# core_logique.net
KiCad netlist of a schematic drawn in Altium Designer
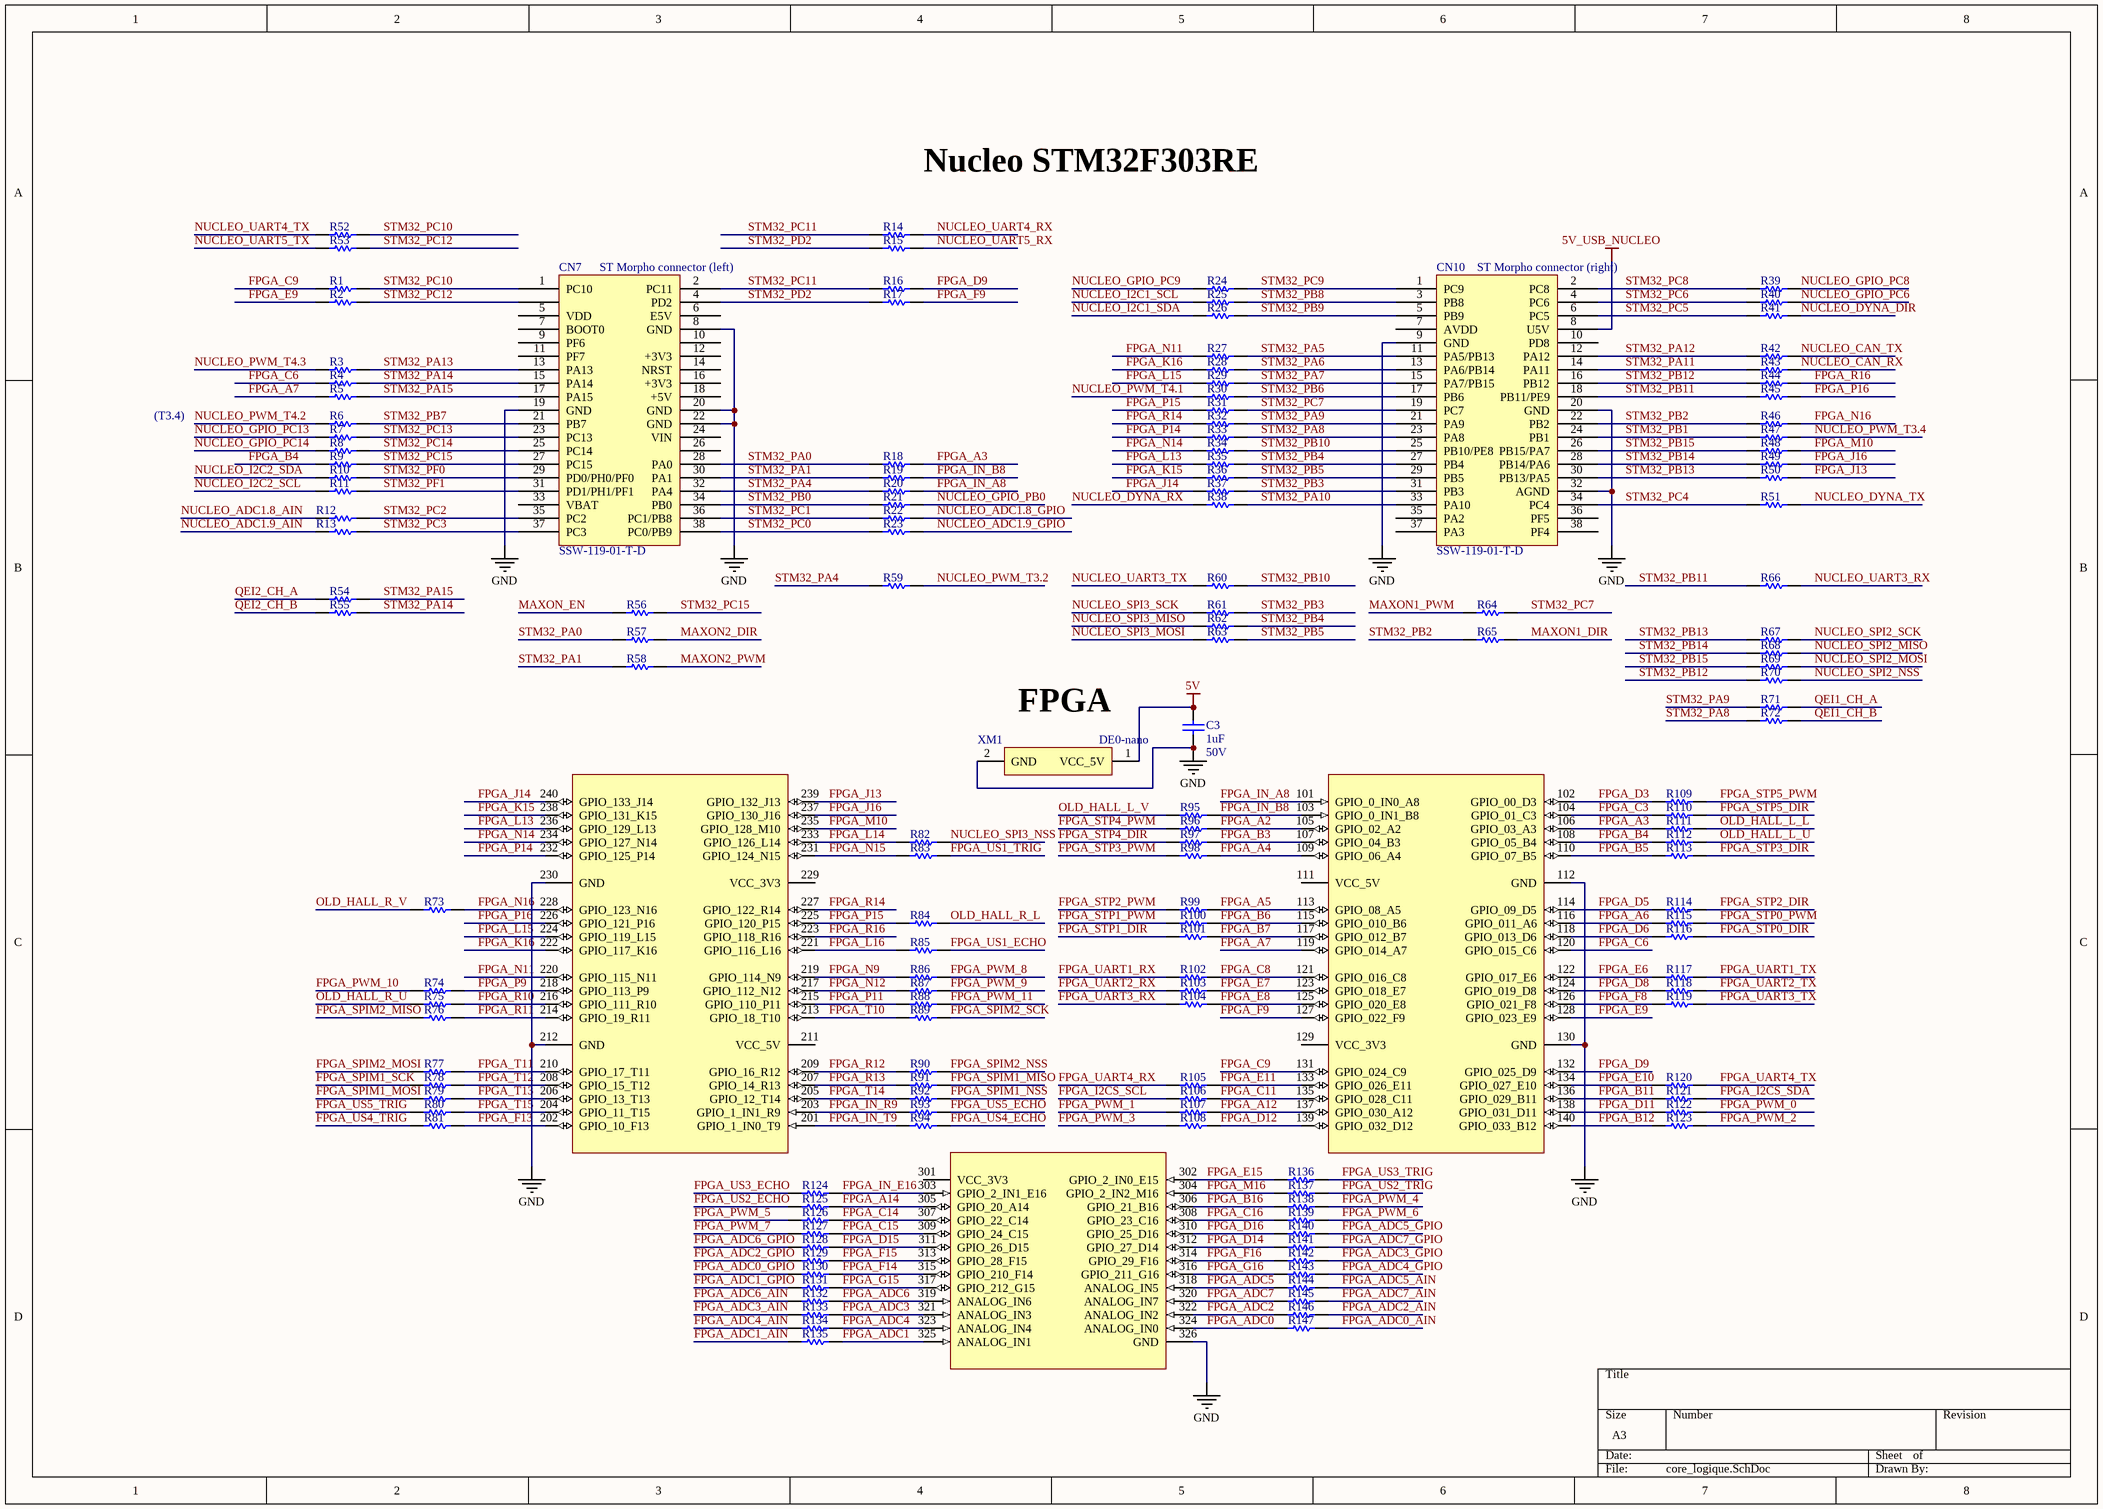
[diagram p0: core_logique.SchDoc]

(export (version "E")
  (design (tool "Eeschema 10.0.6"))
  (components
    (comp (ref "C3")
      (value "1uF")
      (footprint "WCAP-CSGP_0805, 2x1.25x1.25")
      (description "CAP CER 1uF 50V X7R 0805")
      (fields
        (field (name "MANUFACTURER") "Wurth Elektronik")
        (field (name "MANUFACTURER PART NUMBER") "885012207103")
        (field (name "RATEDVOLTAGE") "50V")
      )
      (libsource (lib "Condensateur") (part "WCAP-CSGP, 885012207103"))
    )
    (comp (ref "CN7")
      (value "SSW-119-01-T-D")
      (footprint "Samtec:CONN RCPT .100\" 38POS DUAL TIN")
      (description "CONN RCPT .100\" 38POS DUAL TIN")
      (fields (field (name "MANUFACTURER") "Samtec Inc."))
      (libsource (lib "Samtec") (part "SSW-119-01-T-D"))
    )
    (comp (ref "CN10")
      (value "SSW-119-01-T-D")
      (footprint "Samtec:CONN RCPT .100\" 38POS DUAL TIN")
      (description "CONN RCPT .100\" 38POS DUAL TIN")
      (fields (field (name "MANUFACTURER") "Samtec Inc."))
      (libsource (lib "Samtec") (part "SSW-119-01-T-D"))
    )
    (comp (ref "R1")
      (value "RC0402FR-0722RL")
      (footprint "RESC1005X04N")
      (description "RES SMD 22 OHM 1% 1/16W 0402")
      (fields (field (name "POWER") "63mW") (field (name "MANUFACTURER") "Yageo"))
      (libsource (lib "Resistance") (part "RC0402FR-0722RL"))
    )
    (comp (ref "R2")
      (value "RC0402FR-0722RL")
      (footprint "RESC1005X04N")
      (description "RES SMD 22 OHM 1% 1/16W 0402")
      (fields (field (name "POWER") "63mW") (field (name "MANUFACTURER") "Yageo"))
      (libsource (lib "Resistance") (part "RC0402FR-0722RL"))
    )
    (comp (ref "R3")
      (value "RC0402FR-0722RL")
      (footprint "RESC1005X04N")
      (description "RES SMD 22 OHM 1% 1/16W 0402")
      (fields (field (name "POWER") "63mW") (field (name "MANUFACTURER") "Yageo"))
      (libsource (lib "Resistance") (part "RC0402FR-0722RL"))
    )
    (comp (ref "R4")
      (value "RC0402FR-0722RL")
      (footprint "RESC1005X04N")
      (description "RES SMD 22 OHM 1% 1/16W 0402")
      (fields (field (name "POWER") "63mW") (field (name "MANUFACTURER") "Yageo"))
      (libsource (lib "Resistance") (part "RC0402FR-0722RL"))
    )
    (comp (ref "R5")
      (value "RC0402FR-0722RL")
      (footprint "RESC1005X04N")
      (description "RES SMD 22 OHM 1% 1/16W 0402")
      (fields (field (name "POWER") "63mW") (field (name "MANUFACTURER") "Yageo"))
      (libsource (lib "Resistance") (part "RC0402FR-0722RL"))
    )
    (comp (ref "R6")
      (value "RC0402FR-0722RL")
      (footprint "RESC1005X04N")
      (description "RES SMD 22 OHM 1% 1/16W 0402")
      (fields (field (name "POWER") "63mW") (field (name "MANUFACTURER") "Yageo"))
      (libsource (lib "Resistance") (part "RC0402FR-0722RL"))
    )
    (comp (ref "R7")
      (value "RC0402FR-0722RL")
      (footprint "RESC1005X04N")
      (description "RES SMD 22 OHM 1% 1/16W 0402")
      (fields (field (name "POWER") "63mW") (field (name "MANUFACTURER") "Yageo"))
      (libsource (lib "Resistance") (part "RC0402FR-0722RL"))
    )
    (comp (ref "R8")
      (value "RC0402FR-0722RL")
      (footprint "RESC1005X04N")
      (description "RES SMD 22 OHM 1% 1/16W 0402")
      (fields (field (name "POWER") "63mW") (field (name "MANUFACTURER") "Yageo"))
      (libsource (lib "Resistance") (part "RC0402FR-0722RL"))
    )
    (comp (ref "R9")
      (value "RC0402FR-0722RL")
      (footprint "RESC1005X04N")
      (description "RES SMD 22 OHM 1% 1/16W 0402")
      (fields (field (name "POWER") "63mW") (field (name "MANUFACTURER") "Yageo"))
      (libsource (lib "Resistance") (part "RC0402FR-0722RL"))
    )
    (comp (ref "R10")
      (value "RC0402FR-0722RL")
      (footprint "RESC1005X04N")
      (description "RES SMD 22 OHM 1% 1/16W 0402")
      (fields (field (name "POWER") "63mW") (field (name "MANUFACTURER") "Yageo"))
      (libsource (lib "Resistance") (part "RC0402FR-0722RL"))
    )
    (comp (ref "R11")
      (value "RC0402FR-0722RL")
      (footprint "RESC1005X04N")
      (description "RES SMD 22 OHM 1% 1/16W 0402")
      (fields (field (name "POWER") "63mW") (field (name "MANUFACTURER") "Yageo"))
      (libsource (lib "Resistance") (part "RC0402FR-0722RL"))
    )
    (comp (ref "R12")
      (value "RC0402FR-0722RL")
      (footprint "RESC1005X04N")
      (description "RES SMD 22 OHM 1% 1/16W 0402")
      (fields (field (name "POWER") "63mW") (field (name "MANUFACTURER") "Yageo"))
      (libsource (lib "Resistance") (part "RC0402FR-0722RL"))
    )
    (comp (ref "R13")
      (value "RC0402FR-0722RL")
      (footprint "RESC1005X04N")
      (description "RES SMD 22 OHM 1% 1/16W 0402")
      (fields (field (name "POWER") "63mW") (field (name "MANUFACTURER") "Yageo"))
      (libsource (lib "Resistance") (part "RC0402FR-0722RL"))
    )
    (comp (ref "R14")
      (value "RC0402FR-0722RL")
      (footprint "RESC1005X04N")
      (description "RES SMD 22 OHM 1% 1/16W 0402")
      (fields (field (name "POWER") "63mW") (field (name "MANUFACTURER") "Yageo"))
      (libsource (lib "Resistance") (part "RC0402FR-0722RL"))
    )
    (comp (ref "R15")
      (value "RC0402FR-0722RL")
      (footprint "RESC1005X04N")
      (description "RES SMD 22 OHM 1% 1/16W 0402")
      (fields (field (name "POWER") "63mW") (field (name "MANUFACTURER") "Yageo"))
      (libsource (lib "Resistance") (part "RC0402FR-0722RL"))
    )
    (comp (ref "R16")
      (value "RC0402FR-0722RL")
      (footprint "RESC1005X04N")
      (description "RES SMD 22 OHM 1% 1/16W 0402")
      (fields (field (name "POWER") "63mW") (field (name "MANUFACTURER") "Yageo"))
      (libsource (lib "Resistance") (part "RC0402FR-0722RL"))
    )
    (comp (ref "R17")
      (value "RC0402FR-0722RL")
      (footprint "RESC1005X04N")
      (description "RES SMD 22 OHM 1% 1/16W 0402")
      (fields (field (name "POWER") "63mW") (field (name "MANUFACTURER") "Yageo"))
      (libsource (lib "Resistance") (part "RC0402FR-0722RL"))
    )
    (comp (ref "R18")
      (value "RC0402FR-0722RL")
      (footprint "RESC1005X04N")
      (description "RES SMD 22 OHM 1% 1/16W 0402")
      (fields (field (name "POWER") "63mW") (field (name "MANUFACTURER") "Yageo"))
      (libsource (lib "Resistance") (part "RC0402FR-0722RL"))
    )
    (comp (ref "R19")
      (value "RC0402FR-0722RL")
      (footprint "RESC1005X04N")
      (description "RES SMD 22 OHM 1% 1/16W 0402")
      (fields (field (name "POWER") "63mW") (field (name "MANUFACTURER") "Yageo"))
      (libsource (lib "Resistance") (part "RC0402FR-0722RL"))
    )
    (comp (ref "R20")
      (value "RC0402FR-0722RL")
      (footprint "RESC1005X04N")
      (description "RES SMD 22 OHM 1% 1/16W 0402")
      (fields (field (name "POWER") "63mW") (field (name "MANUFACTURER") "Yageo"))
      (libsource (lib "Resistance") (part "RC0402FR-0722RL"))
    )
    (comp (ref "R21")
      (value "RC0402FR-0722RL")
      (footprint "RESC1005X04N")
      (description "RES SMD 22 OHM 1% 1/16W 0402")
      (fields (field (name "POWER") "63mW") (field (name "MANUFACTURER") "Yageo"))
      (libsource (lib "Resistance") (part "RC0402FR-0722RL"))
    )
    (comp (ref "R22")
      (value "RC0402FR-0722RL")
      (footprint "RESC1005X04N")
      (description "RES SMD 22 OHM 1% 1/16W 0402")
      (fields (field (name "POWER") "63mW") (field (name "MANUFACTURER") "Yageo"))
      (libsource (lib "Resistance") (part "RC0402FR-0722RL"))
    )
    (comp (ref "R23")
      (value "RC0402FR-0722RL")
      (footprint "RESC1005X04N")
      (description "RES SMD 22 OHM 1% 1/16W 0402")
      (fields (field (name "POWER") "63mW") (field (name "MANUFACTURER") "Yageo"))
      (libsource (lib "Resistance") (part "RC0402FR-0722RL"))
    )
    (comp (ref "R24")
      (value "RC0402FR-0722RL")
      (footprint "RESC1005X04N")
      (description "RES SMD 22 OHM 1% 1/16W 0402")
      (fields (field (name "POWER") "63mW") (field (name "MANUFACTURER") "Yageo"))
      (libsource (lib "Resistance") (part "RC0402FR-0722RL"))
    )
    (comp (ref "R25")
      (value "RC0402FR-0722RL")
      (footprint "RESC1005X04N")
      (description "RES SMD 22 OHM 1% 1/16W 0402")
      (fields (field (name "POWER") "63mW") (field (name "MANUFACTURER") "Yageo"))
      (libsource (lib "Resistance") (part "RC0402FR-0722RL"))
    )
    (comp (ref "R26")
      (value "RC0402FR-0722RL")
      (footprint "RESC1005X04N")
      (description "RES SMD 22 OHM 1% 1/16W 0402")
      (fields (field (name "POWER") "63mW") (field (name "MANUFACTURER") "Yageo"))
      (libsource (lib "Resistance") (part "RC0402FR-0722RL"))
    )
    (comp (ref "R27")
      (value "RC0402FR-0722RL")
      (footprint "RESC1005X04N")
      (description "RES SMD 22 OHM 1% 1/16W 0402")
      (fields (field (name "POWER") "63mW") (field (name "MANUFACTURER") "Yageo"))
      (libsource (lib "Resistance") (part "RC0402FR-0722RL"))
    )
    (comp (ref "R28")
      (value "RC0402FR-0722RL")
      (footprint "RESC1005X04N")
      (description "RES SMD 22 OHM 1% 1/16W 0402")
      (fields (field (name "POWER") "63mW") (field (name "MANUFACTURER") "Yageo"))
      (libsource (lib "Resistance") (part "RC0402FR-0722RL"))
    )
    (comp (ref "R29")
      (value "RC0402FR-0722RL")
      (footprint "RESC1005X04N")
      (description "RES SMD 22 OHM 1% 1/16W 0402")
      (fields (field (name "POWER") "63mW") (field (name "MANUFACTURER") "Yageo"))
      (libsource (lib "Resistance") (part "RC0402FR-0722RL"))
    )
    (comp (ref "R30")
      (value "RC0402FR-0722RL")
      (footprint "RESC1005X04N")
      (description "RES SMD 22 OHM 1% 1/16W 0402")
      (fields (field (name "POWER") "63mW") (field (name "MANUFACTURER") "Yageo"))
      (libsource (lib "Resistance") (part "RC0402FR-0722RL"))
    )
    (comp (ref "R31")
      (value "RC0402FR-0722RL")
      (footprint "RESC1005X04N")
      (description "RES SMD 22 OHM 1% 1/16W 0402")
      (fields (field (name "POWER") "63mW") (field (name "MANUFACTURER") "Yageo"))
      (libsource (lib "Resistance") (part "RC0402FR-0722RL"))
    )
    (comp (ref "R32")
      (value "RC0402FR-0722RL")
      (footprint "RESC1005X04N")
      (description "RES SMD 22 OHM 1% 1/16W 0402")
      (fields (field (name "POWER") "63mW") (field (name "MANUFACTURER") "Yageo"))
      (libsource (lib "Resistance") (part "RC0402FR-0722RL"))
    )
    (comp (ref "R33")
      (value "RC0402FR-0722RL")
      (footprint "RESC1005X04N")
      (description "RES SMD 22 OHM 1% 1/16W 0402")
      (fields (field (name "POWER") "63mW") (field (name "MANUFACTURER") "Yageo"))
      (libsource (lib "Resistance") (part "RC0402FR-0722RL"))
    )
    (comp (ref "R34")
      (value "RC0402FR-0722RL")
      (footprint "RESC1005X04N")
      (description "RES SMD 22 OHM 1% 1/16W 0402")
      (fields (field (name "POWER") "63mW") (field (name "MANUFACTURER") "Yageo"))
      (libsource (lib "Resistance") (part "RC0402FR-0722RL"))
    )
    (comp (ref "R35")
      (value "RC0402FR-0722RL")
      (footprint "RESC1005X04N")
      (description "RES SMD 22 OHM 1% 1/16W 0402")
      (fields (field (name "POWER") "63mW") (field (name "MANUFACTURER") "Yageo"))
      (libsource (lib "Resistance") (part "RC0402FR-0722RL"))
    )
    (comp (ref "R36")
      (value "RC0402FR-0722RL")
      (footprint "RESC1005X04N")
      (description "RES SMD 22 OHM 1% 1/16W 0402")
      (fields (field (name "POWER") "63mW") (field (name "MANUFACTURER") "Yageo"))
      (libsource (lib "Resistance") (part "RC0402FR-0722RL"))
    )
    (comp (ref "R37")
      (value "RC0402FR-0722RL")
      (footprint "RESC1005X04N")
      (description "RES SMD 22 OHM 1% 1/16W 0402")
      (fields (field (name "POWER") "63mW") (field (name "MANUFACTURER") "Yageo"))
      (libsource (lib "Resistance") (part "RC0402FR-0722RL"))
    )
    (comp (ref "R38")
      (value "RC0402FR-0722RL")
      (footprint "RESC1005X04N")
      (description "RES SMD 22 OHM 1% 1/16W 0402")
      (fields (field (name "POWER") "63mW") (field (name "MANUFACTURER") "Yageo"))
      (libsource (lib "Resistance") (part "RC0402FR-0722RL"))
    )
    (comp (ref "R39")
      (value "RC0402FR-0722RL")
      (footprint "RESC1005X04N")
      (description "RES SMD 22 OHM 1% 1/16W 0402")
      (fields (field (name "POWER") "63mW") (field (name "MANUFACTURER") "Yageo"))
      (libsource (lib "Resistance") (part "RC0402FR-0722RL"))
    )
    (comp (ref "R40")
      (value "RC0402FR-0722RL")
      (footprint "RESC1005X04N")
      (description "RES SMD 22 OHM 1% 1/16W 0402")
      (fields (field (name "POWER") "63mW") (field (name "MANUFACTURER") "Yageo"))
      (libsource (lib "Resistance") (part "RC0402FR-0722RL"))
    )
    (comp (ref "R41")
      (value "RC0402FR-0722RL")
      (footprint "RESC1005X04N")
      (description "RES SMD 22 OHM 1% 1/16W 0402")
      (fields (field (name "POWER") "63mW") (field (name "MANUFACTURER") "Yageo"))
      (libsource (lib "Resistance") (part "RC0402FR-0722RL"))
    )
    (comp (ref "R42")
      (value "RC0402FR-0722RL")
      (footprint "RESC1005X04N")
      (description "RES SMD 22 OHM 1% 1/16W 0402")
      (fields (field (name "POWER") "63mW") (field (name "MANUFACTURER") "Yageo"))
      (libsource (lib "Resistance") (part "RC0402FR-0722RL"))
    )
    (comp (ref "R43")
      (value "RC0402FR-0722RL")
      (footprint "RESC1005X04N")
      (description "RES SMD 22 OHM 1% 1/16W 0402")
      (fields (field (name "POWER") "63mW") (field (name "MANUFACTURER") "Yageo"))
      (libsource (lib "Resistance") (part "RC0402FR-0722RL"))
    )
    (comp (ref "R44")
      (value "RC0402FR-0722RL")
      (footprint "RESC1005X04N")
      (description "RES SMD 22 OHM 1% 1/16W 0402")
      (fields (field (name "POWER") "63mW") (field (name "MANUFACTURER") "Yageo"))
      (libsource (lib "Resistance") (part "RC0402FR-0722RL"))
    )
    (comp (ref "R45")
      (value "RC0402FR-0722RL")
      (footprint "RESC1005X04N")
      (description "RES SMD 22 OHM 1% 1/16W 0402")
      (fields (field (name "POWER") "63mW") (field (name "MANUFACTURER") "Yageo"))
      (libsource (lib "Resistance") (part "RC0402FR-0722RL"))
    )
    (comp (ref "R46")
      (value "RC0402FR-0722RL")
      (footprint "RESC1005X04N")
      (description "RES SMD 22 OHM 1% 1/16W 0402")
      (fields (field (name "POWER") "63mW") (field (name "MANUFACTURER") "Yageo"))
      (libsource (lib "Resistance") (part "RC0402FR-0722RL"))
    )
    (comp (ref "R47")
      (value "RC0402FR-0722RL")
      (footprint "RESC1005X04N")
      (description "RES SMD 22 OHM 1% 1/16W 0402")
      (fields (field (name "POWER") "63mW") (field (name "MANUFACTURER") "Yageo"))
      (libsource (lib "Resistance") (part "RC0402FR-0722RL"))
    )
    (comp (ref "R48")
      (value "RC0402FR-0722RL")
      (footprint "RESC1005X04N")
      (description "RES SMD 22 OHM 1% 1/16W 0402")
      (fields (field (name "POWER") "63mW") (field (name "MANUFACTURER") "Yageo"))
      (libsource (lib "Resistance") (part "RC0402FR-0722RL"))
    )
    (comp (ref "R49")
      (value "RC0402FR-0722RL")
      (footprint "RESC1005X04N")
      (description "RES SMD 22 OHM 1% 1/16W 0402")
      (fields (field (name "POWER") "63mW") (field (name "MANUFACTURER") "Yageo"))
      (libsource (lib "Resistance") (part "RC0402FR-0722RL"))
    )
    (comp (ref "R50")
      (value "RC0402FR-0722RL")
      (footprint "RESC1005X04N")
      (description "RES SMD 22 OHM 1% 1/16W 0402")
      (fields (field (name "POWER") "63mW") (field (name "MANUFACTURER") "Yageo"))
      (libsource (lib "Resistance") (part "RC0402FR-0722RL"))
    )
    (comp (ref "R51")
      (value "RC0402FR-0722RL")
      (footprint "RESC1005X04N")
      (description "RES SMD 22 OHM 1% 1/16W 0402")
      (fields (field (name "POWER") "63mW") (field (name "MANUFACTURER") "Yageo"))
      (libsource (lib "Resistance") (part "RC0402FR-0722RL"))
    )
    (comp (ref "R52")
      (value "RC0402FR-0722RL")
      (footprint "RESC1005X04N")
      (description "RES SMD 22 OHM 1% 1/16W 0402")
      (fields (field (name "POWER") "63mW") (field (name "MANUFACTURER") "Yageo"))
      (libsource (lib "Resistance") (part "RC0402FR-0722RL"))
    )
    (comp (ref "R53")
      (value "RC0402FR-0722RL")
      (footprint "RESC1005X04N")
      (description "RES SMD 22 OHM 1% 1/16W 0402")
      (fields (field (name "POWER") "63mW") (field (name "MANUFACTURER") "Yageo"))
      (libsource (lib "Resistance") (part "RC0402FR-0722RL"))
    )
    (comp (ref "R54")
      (value "RC0402FR-0722RL")
      (footprint "RESC1005X04N")
      (description "RES SMD 22 OHM 1% 1/16W 0402")
      (fields (field (name "POWER") "63mW") (field (name "MANUFACTURER") "Yageo"))
      (libsource (lib "Resistance") (part "RC0402FR-0722RL"))
    )
    (comp (ref "R55")
      (value "RC0402FR-0722RL")
      (footprint "RESC1005X04N")
      (description "RES SMD 22 OHM 1% 1/16W 0402")
      (fields (field (name "POWER") "63mW") (field (name "MANUFACTURER") "Yageo"))
      (libsource (lib "Resistance") (part "RC0402FR-0722RL"))
    )
    (comp (ref "R56")
      (value "RC0402FR-0722RL")
      (footprint "RESC1005X04N")
      (description "RES SMD 22 OHM 1% 1/16W 0402")
      (fields (field (name "POWER") "63mW") (field (name "MANUFACTURER") "Yageo"))
      (libsource (lib "Resistance") (part "RC0402FR-0722RL"))
    )
    (comp (ref "R57")
      (value "RC0402FR-0722RL")
      (footprint "RESC1005X04N")
      (description "RES SMD 22 OHM 1% 1/16W 0402")
      (fields (field (name "POWER") "63mW") (field (name "MANUFACTURER") "Yageo"))
      (libsource (lib "Resistance") (part "RC0402FR-0722RL"))
    )
    (comp (ref "R58")
      (value "RC0402FR-0722RL")
      (footprint "RESC1005X04N")
      (description "RES SMD 22 OHM 1% 1/16W 0402")
      (fields (field (name "POWER") "63mW") (field (name "MANUFACTURER") "Yageo"))
      (libsource (lib "Resistance") (part "RC0402FR-0722RL"))
    )
    (comp (ref "R59")
      (value "RC0402FR-0722RL")
      (footprint "RESC1005X04N")
      (description "RES SMD 22 OHM 1% 1/16W 0402")
      (fields (field (name "POWER") "63mW") (field (name "MANUFACTURER") "Yageo"))
      (libsource (lib "Resistance") (part "RC0402FR-0722RL"))
    )
    (comp (ref "R60")
      (value "RC0402FR-0722RL")
      (footprint "RESC1005X04N")
      (description "RES SMD 22 OHM 1% 1/16W 0402")
      (fields (field (name "POWER") "63mW") (field (name "MANUFACTURER") "Yageo"))
      (libsource (lib "Resistance") (part "RC0402FR-0722RL"))
    )
    (comp (ref "R61")
      (value "RC0402FR-0722RL")
      (footprint "RESC1005X04N")
      (description "RES SMD 22 OHM 1% 1/16W 0402")
      (fields (field (name "POWER") "63mW") (field (name "MANUFACTURER") "Yageo"))
      (libsource (lib "Resistance") (part "RC0402FR-0722RL"))
    )
    (comp (ref "R62")
      (value "RC0402FR-0722RL")
      (footprint "RESC1005X04N")
      (description "RES SMD 22 OHM 1% 1/16W 0402")
      (fields (field (name "POWER") "63mW") (field (name "MANUFACTURER") "Yageo"))
      (libsource (lib "Resistance") (part "RC0402FR-0722RL"))
    )
    (comp (ref "R63")
      (value "RC0402FR-0722RL")
      (footprint "RESC1005X04N")
      (description "RES SMD 22 OHM 1% 1/16W 0402")
      (fields (field (name "POWER") "63mW") (field (name "MANUFACTURER") "Yageo"))
      (libsource (lib "Resistance") (part "RC0402FR-0722RL"))
    )
    (comp (ref "R64")
      (value "RC0402FR-0722RL")
      (footprint "RESC1005X04N")
      (description "RES SMD 22 OHM 1% 1/16W 0402")
      (fields (field (name "POWER") "63mW") (field (name "MANUFACTURER") "Yageo"))
      (libsource (lib "Resistance") (part "RC0402FR-0722RL"))
    )
    (comp (ref "R65")
      (value "RC0402FR-0722RL")
      (footprint "RESC1005X04N")
      (description "RES SMD 22 OHM 1% 1/16W 0402")
      (fields (field (name "POWER") "63mW") (field (name "MANUFACTURER") "Yageo"))
      (libsource (lib "Resistance") (part "RC0402FR-0722RL"))
    )
    (comp (ref "R66")
      (value "RC0402FR-0722RL")
      (footprint "RESC1005X04N")
      (description "RES SMD 22 OHM 1% 1/16W 0402")
      (fields (field (name "POWER") "63mW") (field (name "MANUFACTURER") "Yageo"))
      (libsource (lib "Resistance") (part "RC0402FR-0722RL"))
    )
    (comp (ref "R67")
      (value "RC0402FR-0722RL")
      (footprint "RESC1005X04N")
      (description "RES SMD 22 OHM 1% 1/16W 0402")
      (fields (field (name "POWER") "63mW") (field (name "MANUFACTURER") "Yageo"))
      (libsource (lib "Resistance") (part "RC0402FR-0722RL"))
    )
    (comp (ref "R68")
      (value "RC0402FR-0722RL")
      (footprint "RESC1005X04N")
      (description "RES SMD 22 OHM 1% 1/16W 0402")
      (fields (field (name "POWER") "63mW") (field (name "MANUFACTURER") "Yageo"))
      (libsource (lib "Resistance") (part "RC0402FR-0722RL"))
    )
    (comp (ref "R69")
      (value "RC0402FR-0722RL")
      (footprint "RESC1005X04N")
      (description "RES SMD 22 OHM 1% 1/16W 0402")
      (fields (field (name "POWER") "63mW") (field (name "MANUFACTURER") "Yageo"))
      (libsource (lib "Resistance") (part "RC0402FR-0722RL"))
    )
    (comp (ref "R70")
      (value "RC0402FR-0722RL")
      (footprint "RESC1005X04N")
      (description "RES SMD 22 OHM 1% 1/16W 0402")
      (fields (field (name "POWER") "63mW") (field (name "MANUFACTURER") "Yageo"))
      (libsource (lib "Resistance") (part "RC0402FR-0722RL"))
    )
    (comp (ref "R71")
      (value "RC0402FR-0722RL")
      (footprint "RESC1005X04N")
      (description "RES SMD 22 OHM 1% 1/16W 0402")
      (fields (field (name "POWER") "63mW") (field (name "MANUFACTURER") "Yageo"))
      (libsource (lib "Resistance") (part "RC0402FR-0722RL"))
    )
    (comp (ref "R72")
      (value "RC0402FR-0722RL")
      (footprint "RESC1005X04N")
      (description "RES SMD 22 OHM 1% 1/16W 0402")
      (fields (field (name "POWER") "63mW") (field (name "MANUFACTURER") "Yageo"))
      (libsource (lib "Resistance") (part "RC0402FR-0722RL"))
    )
    (comp (ref "R73")
      (value "RC0402FR-0722RL")
      (footprint "RESC1005X04N")
      (description "RES SMD 22 OHM 1% 1/16W 0402")
      (fields (field (name "POWER") "63mW") (field (name "MANUFACTURER") "Yageo"))
      (libsource (lib "Resistance") (part "RC0402FR-0722RL"))
    )
    (comp (ref "R74")
      (value "RC0402FR-0722RL")
      (footprint "RESC1005X04N")
      (description "RES SMD 22 OHM 1% 1/16W 0402")
      (fields (field (name "POWER") "63mW") (field (name "MANUFACTURER") "Yageo"))
      (libsource (lib "Resistance") (part "RC0402FR-0722RL"))
    )
    (comp (ref "R75")
      (value "RC0402FR-0722RL")
      (footprint "RESC1005X04N")
      (description "RES SMD 22 OHM 1% 1/16W 0402")
      (fields (field (name "POWER") "63mW") (field (name "MANUFACTURER") "Yageo"))
      (libsource (lib "Resistance") (part "RC0402FR-0722RL"))
    )
    (comp (ref "R76")
      (value "RC0402FR-0722RL")
      (footprint "RESC1005X04N")
      (description "RES SMD 22 OHM 1% 1/16W 0402")
      (fields (field (name "POWER") "63mW") (field (name "MANUFACTURER") "Yageo"))
      (libsource (lib "Resistance") (part "RC0402FR-0722RL"))
    )
    (comp (ref "R77")
      (value "RC0402FR-0722RL")
      (footprint "RESC1005X04N")
      (description "RES SMD 22 OHM 1% 1/16W 0402")
      (fields (field (name "POWER") "63mW") (field (name "MANUFACTURER") "Yageo"))
      (libsource (lib "Resistance") (part "RC0402FR-0722RL"))
    )
    (comp (ref "R78")
      (value "RC0402FR-0722RL")
      (footprint "RESC1005X04N")
      (description "RES SMD 22 OHM 1% 1/16W 0402")
      (fields (field (name "POWER") "63mW") (field (name "MANUFACTURER") "Yageo"))
      (libsource (lib "Resistance") (part "RC0402FR-0722RL"))
    )
    (comp (ref "R79")
      (value "RC0402FR-0722RL")
      (footprint "RESC1005X04N")
      (description "RES SMD 22 OHM 1% 1/16W 0402")
      (fields (field (name "POWER") "63mW") (field (name "MANUFACTURER") "Yageo"))
      (libsource (lib "Resistance") (part "RC0402FR-0722RL"))
    )
    (comp (ref "R80")
      (value "RC0402FR-0722RL")
      (footprint "RESC1005X04N")
      (description "RES SMD 22 OHM 1% 1/16W 0402")
      (fields (field (name "POWER") "63mW") (field (name "MANUFACTURER") "Yageo"))
      (libsource (lib "Resistance") (part "RC0402FR-0722RL"))
    )
    (comp (ref "R81")
      (value "RC0402FR-0722RL")
      (footprint "RESC1005X04N")
      (description "RES SMD 22 OHM 1% 1/16W 0402")
      (fields (field (name "POWER") "63mW") (field (name "MANUFACTURER") "Yageo"))
      (libsource (lib "Resistance") (part "RC0402FR-0722RL"))
    )
    (comp (ref "R82")
      (value "RC0402FR-0722RL")
      (footprint "RESC1005X04N")
      (description "RES SMD 22 OHM 1% 1/16W 0402")
      (fields (field (name "POWER") "63mW") (field (name "MANUFACTURER") "Yageo"))
      (libsource (lib "Resistance") (part "RC0402FR-0722RL"))
    )
    (comp (ref "R83")
      (value "RC0402FR-0722RL")
      (footprint "RESC1005X04N")
      (description "RES SMD 22 OHM 1% 1/16W 0402")
      (fields (field (name "POWER") "63mW") (field (name "MANUFACTURER") "Yageo"))
      (libsource (lib "Resistance") (part "RC0402FR-0722RL"))
    )
    (comp (ref "R84")
      (value "RC0402FR-0722RL")
      (footprint "RESC1005X04N")
      (description "RES SMD 22 OHM 1% 1/16W 0402")
      (fields (field (name "POWER") "63mW") (field (name "MANUFACTURER") "Yageo"))
      (libsource (lib "Resistance") (part "RC0402FR-0722RL"))
    )
    (comp (ref "R85")
      (value "RC0402FR-0722RL")
      (footprint "RESC1005X04N")
      (description "RES SMD 22 OHM 1% 1/16W 0402")
      (fields (field (name "POWER") "63mW") (field (name "MANUFACTURER") "Yageo"))
      (libsource (lib "Resistance") (part "RC0402FR-0722RL"))
    )
    (comp (ref "R86")
      (value "RC0402FR-0722RL")
      (footprint "RESC1005X04N")
      (description "RES SMD 22 OHM 1% 1/16W 0402")
      (fields (field (name "POWER") "63mW") (field (name "MANUFACTURER") "Yageo"))
      (libsource (lib "Resistance") (part "RC0402FR-0722RL"))
    )
    (comp (ref "R87")
      (value "RC0402FR-0722RL")
      (footprint "RESC1005X04N")
      (description "RES SMD 22 OHM 1% 1/16W 0402")
      (fields (field (name "POWER") "63mW") (field (name "MANUFACTURER") "Yageo"))
      (libsource (lib "Resistance") (part "RC0402FR-0722RL"))
    )
    (comp (ref "R88")
      (value "RC0402FR-0722RL")
      (footprint "RESC1005X04N")
      (description "RES SMD 22 OHM 1% 1/16W 0402")
      (fields (field (name "POWER") "63mW") (field (name "MANUFACTURER") "Yageo"))
      (libsource (lib "Resistance") (part "RC0402FR-0722RL"))
    )
    (comp (ref "R89")
      (value "RC0402FR-0722RL")
      (footprint "RESC1005X04N")
      (description "RES SMD 22 OHM 1% 1/16W 0402")
      (fields (field (name "POWER") "63mW") (field (name "MANUFACTURER") "Yageo"))
      (libsource (lib "Resistance") (part "RC0402FR-0722RL"))
    )
    (comp (ref "R90")
      (value "RC0402FR-0722RL")
      (footprint "RESC1005X04N")
      (description "RES SMD 22 OHM 1% 1/16W 0402")
      (fields (field (name "POWER") "63mW") (field (name "MANUFACTURER") "Yageo"))
      (libsource (lib "Resistance") (part "RC0402FR-0722RL"))
    )
    (comp (ref "R91")
      (value "RC0402FR-0722RL")
      (footprint "RESC1005X04N")
      (description "RES SMD 22 OHM 1% 1/16W 0402")
      (fields (field (name "POWER") "63mW") (field (name "MANUFACTURER") "Yageo"))
      (libsource (lib "Resistance") (part "RC0402FR-0722RL"))
    )
    (comp (ref "R92")
      (value "RC0402FR-0722RL")
      (footprint "RESC1005X04N")
      (description "RES SMD 22 OHM 1% 1/16W 0402")
      (fields (field (name "POWER") "63mW") (field (name "MANUFACTURER") "Yageo"))
      (libsource (lib "Resistance") (part "RC0402FR-0722RL"))
    )
    (comp (ref "R93")
      (value "RC0402FR-0722RL")
      (footprint "RESC1005X04N")
      (description "RES SMD 22 OHM 1% 1/16W 0402")
      (fields (field (name "POWER") "63mW") (field (name "MANUFACTURER") "Yageo"))
      (libsource (lib "Resistance") (part "RC0402FR-0722RL"))
    )
    (comp (ref "R94")
      (value "RC0402FR-0722RL")
      (footprint "RESC1005X04N")
      (description "RES SMD 22 OHM 1% 1/16W 0402")
      (fields (field (name "POWER") "63mW") (field (name "MANUFACTURER") "Yageo"))
      (libsource (lib "Resistance") (part "RC0402FR-0722RL"))
    )
    (comp (ref "R95")
      (value "RC0402FR-0722RL")
      (footprint "RESC1005X04N")
      (description "RES SMD 22 OHM 1% 1/16W 0402")
      (fields (field (name "POWER") "63mW") (field (name "MANUFACTURER") "Yageo"))
      (libsource (lib "Resistance") (part "RC0402FR-0722RL"))
    )
    (comp (ref "R96")
      (value "RC0402FR-0722RL")
      (footprint "RESC1005X04N")
      (description "RES SMD 22 OHM 1% 1/16W 0402")
      (fields (field (name "POWER") "63mW") (field (name "MANUFACTURER") "Yageo"))
      (libsource (lib "Resistance") (part "RC0402FR-0722RL"))
    )
    (comp (ref "R97")
      (value "RC0402FR-0722RL")
      (footprint "RESC1005X04N")
      (description "RES SMD 22 OHM 1% 1/16W 0402")
      (fields (field (name "POWER") "63mW") (field (name "MANUFACTURER") "Yageo"))
      (libsource (lib "Resistance") (part "RC0402FR-0722RL"))
    )
    (comp (ref "R98")
      (value "RC0402FR-0722RL")
      (footprint "RESC1005X04N")
      (description "RES SMD 22 OHM 1% 1/16W 0402")
      (fields (field (name "POWER") "63mW") (field (name "MANUFACTURER") "Yageo"))
      (libsource (lib "Resistance") (part "RC0402FR-0722RL"))
    )
    (comp (ref "R99")
      (value "RC0402FR-0722RL")
      (footprint "RESC1005X04N")
      (description "RES SMD 22 OHM 1% 1/16W 0402")
      (fields (field (name "POWER") "63mW") (field (name "MANUFACTURER") "Yageo"))
      (libsource (lib "Resistance") (part "RC0402FR-0722RL"))
    )
    (comp (ref "R100")
      (value "RC0402FR-0722RL")
      (footprint "RESC1005X04N")
      (description "RES SMD 22 OHM 1% 1/16W 0402")
      (fields (field (name "POWER") "63mW") (field (name "MANUFACTURER") "Yageo"))
      (libsource (lib "Resistance") (part "RC0402FR-0722RL"))
    )
    (comp (ref "R101")
      (value "RC0402FR-0722RL")
      (footprint "RESC1005X04N")
      (description "RES SMD 22 OHM 1% 1/16W 0402")
      (fields (field (name "POWER") "63mW") (field (name "MANUFACTURER") "Yageo"))
      (libsource (lib "Resistance") (part "RC0402FR-0722RL"))
    )
    (comp (ref "R102")
      (value "RC0402FR-0722RL")
      (footprint "RESC1005X04N")
      (description "RES SMD 22 OHM 1% 1/16W 0402")
      (fields (field (name "POWER") "63mW") (field (name "MANUFACTURER") "Yageo"))
      (libsource (lib "Resistance") (part "RC0402FR-0722RL"))
    )
    (comp (ref "R103")
      (value "RC0402FR-0722RL")
      (footprint "RESC1005X04N")
      (description "RES SMD 22 OHM 1% 1/16W 0402")
      (fields (field (name "POWER") "63mW") (field (name "MANUFACTURER") "Yageo"))
      (libsource (lib "Resistance") (part "RC0402FR-0722RL"))
    )
    (comp (ref "R104")
      (value "RC0402FR-0722RL")
      (footprint "RESC1005X04N")
      (description "RES SMD 22 OHM 1% 1/16W 0402")
      (fields (field (name "POWER") "63mW") (field (name "MANUFACTURER") "Yageo"))
      (libsource (lib "Resistance") (part "RC0402FR-0722RL"))
    )
    (comp (ref "R105")
      (value "RC0402FR-0722RL")
      (footprint "RESC1005X04N")
      (description "RES SMD 22 OHM 1% 1/16W 0402")
      (fields (field (name "POWER") "63mW") (field (name "MANUFACTURER") "Yageo"))
      (libsource (lib "Resistance") (part "RC0402FR-0722RL"))
    )
    (comp (ref "R106")
      (value "RC0402FR-0722RL")
      (footprint "RESC1005X04N")
      (description "RES SMD 22 OHM 1% 1/16W 0402")
      (fields (field (name "POWER") "63mW") (field (name "MANUFACTURER") "Yageo"))
      (libsource (lib "Resistance") (part "RC0402FR-0722RL"))
    )
    (comp (ref "R107")
      (value "RC0402FR-0722RL")
      (footprint "RESC1005X04N")
      (description "RES SMD 22 OHM 1% 1/16W 0402")
      (fields (field (name "POWER") "63mW") (field (name "MANUFACTURER") "Yageo"))
      (libsource (lib "Resistance") (part "RC0402FR-0722RL"))
    )
    (comp (ref "R108")
      (value "RC0402FR-0722RL")
      (footprint "RESC1005X04N")
      (description "RES SMD 22 OHM 1% 1/16W 0402")
      (fields (field (name "POWER") "63mW") (field (name "MANUFACTURER") "Yageo"))
      (libsource (lib "Resistance") (part "RC0402FR-0722RL"))
    )
    (comp (ref "R109")
      (value "RC0402FR-0722RL")
      (footprint "RESC1005X04N")
      (description "RES SMD 22 OHM 1% 1/16W 0402")
      (fields (field (name "POWER") "63mW") (field (name "MANUFACTURER") "Yageo"))
      (libsource (lib "Resistance") (part "RC0402FR-0722RL"))
    )
    (comp (ref "R110")
      (value "RC0402FR-0722RL")
      (footprint "RESC1005X04N")
      (description "RES SMD 22 OHM 1% 1/16W 0402")
      (fields (field (name "POWER") "63mW") (field (name "MANUFACTURER") "Yageo"))
      (libsource (lib "Resistance") (part "RC0402FR-0722RL"))
    )
    (comp (ref "R111")
      (value "RC0402FR-0722RL")
      (footprint "RESC1005X04N")
      (description "RES SMD 22 OHM 1% 1/16W 0402")
      (fields (field (name "POWER") "63mW") (field (name "MANUFACTURER") "Yageo"))
      (libsource (lib "Resistance") (part "RC0402FR-0722RL"))
    )
    (comp (ref "R112")
      (value "RC0402FR-0722RL")
      (footprint "RESC1005X04N")
      (description "RES SMD 22 OHM 1% 1/16W 0402")
      (fields (field (name "POWER") "63mW") (field (name "MANUFACTURER") "Yageo"))
      (libsource (lib "Resistance") (part "RC0402FR-0722RL"))
    )
    (comp (ref "R113")
      (value "RC0402FR-0722RL")
      (footprint "RESC1005X04N")
      (description "RES SMD 22 OHM 1% 1/16W 0402")
      (fields (field (name "POWER") "63mW") (field (name "MANUFACTURER") "Yageo"))
      (libsource (lib "Resistance") (part "RC0402FR-0722RL"))
    )
    (comp (ref "R114")
      (value "RC0402FR-0722RL")
      (footprint "RESC1005X04N")
      (description "RES SMD 22 OHM 1% 1/16W 0402")
      (fields (field (name "POWER") "63mW") (field (name "MANUFACTURER") "Yageo"))
      (libsource (lib "Resistance") (part "RC0402FR-0722RL"))
    )
    (comp (ref "R115")
      (value "RC0402FR-0722RL")
      (footprint "RESC1005X04N")
      (description "RES SMD 22 OHM 1% 1/16W 0402")
      (fields (field (name "POWER") "63mW") (field (name "MANUFACTURER") "Yageo"))
      (libsource (lib "Resistance") (part "RC0402FR-0722RL"))
    )
    (comp (ref "R116")
      (value "RC0402FR-0722RL")
      (footprint "RESC1005X04N")
      (description "RES SMD 22 OHM 1% 1/16W 0402")
      (fields (field (name "POWER") "63mW") (field (name "MANUFACTURER") "Yageo"))
      (libsource (lib "Resistance") (part "RC0402FR-0722RL"))
    )
    (comp (ref "R117")
      (value "RC0402FR-0722RL")
      (footprint "RESC1005X04N")
      (description "RES SMD 22 OHM 1% 1/16W 0402")
      (fields (field (name "POWER") "63mW") (field (name "MANUFACTURER") "Yageo"))
      (libsource (lib "Resistance") (part "RC0402FR-0722RL"))
    )
    (comp (ref "R118")
      (value "RC0402FR-0722RL")
      (footprint "RESC1005X04N")
      (description "RES SMD 22 OHM 1% 1/16W 0402")
      (fields (field (name "POWER") "63mW") (field (name "MANUFACTURER") "Yageo"))
      (libsource (lib "Resistance") (part "RC0402FR-0722RL"))
    )
    (comp (ref "R119")
      (value "RC0402FR-0722RL")
      (footprint "RESC1005X04N")
      (description "RES SMD 22 OHM 1% 1/16W 0402")
      (fields (field (name "POWER") "63mW") (field (name "MANUFACTURER") "Yageo"))
      (libsource (lib "Resistance") (part "RC0402FR-0722RL"))
    )
    (comp (ref "R120")
      (value "RC0402FR-0722RL")
      (footprint "RESC1005X04N")
      (description "RES SMD 22 OHM 1% 1/16W 0402")
      (fields (field (name "POWER") "63mW") (field (name "MANUFACTURER") "Yageo"))
      (libsource (lib "Resistance") (part "RC0402FR-0722RL"))
    )
    (comp (ref "R121")
      (value "RC0402FR-0722RL")
      (footprint "RESC1005X04N")
      (description "RES SMD 22 OHM 1% 1/16W 0402")
      (fields (field (name "POWER") "63mW") (field (name "MANUFACTURER") "Yageo"))
      (libsource (lib "Resistance") (part "RC0402FR-0722RL"))
    )
    (comp (ref "R122")
      (value "RC0402FR-0722RL")
      (footprint "RESC1005X04N")
      (description "RES SMD 22 OHM 1% 1/16W 0402")
      (fields (field (name "POWER") "63mW") (field (name "MANUFACTURER") "Yageo"))
      (libsource (lib "Resistance") (part "RC0402FR-0722RL"))
    )
    (comp (ref "R123")
      (value "RC0402FR-0722RL")
      (footprint "RESC1005X04N")
      (description "RES SMD 22 OHM 1% 1/16W 0402")
      (fields (field (name "POWER") "63mW") (field (name "MANUFACTURER") "Yageo"))
      (libsource (lib "Resistance") (part "RC0402FR-0722RL"))
    )
    (comp (ref "R124")
      (value "RC0402FR-0722RL")
      (footprint "RESC1005X04N")
      (description "RES SMD 22 OHM 1% 1/16W 0402")
      (fields (field (name "POWER") "63mW") (field (name "MANUFACTURER") "Yageo"))
      (libsource (lib "Resistance") (part "RC0402FR-0722RL"))
    )
    (comp (ref "R125")
      (value "RC0402FR-0722RL")
      (footprint "RESC1005X04N")
      (description "RES SMD 22 OHM 1% 1/16W 0402")
      (fields (field (name "POWER") "63mW") (field (name "MANUFACTURER") "Yageo"))
      (libsource (lib "Resistance") (part "RC0402FR-0722RL"))
    )
    (comp (ref "R126")
      (value "RC0402FR-0722RL")
      (footprint "RESC1005X04N")
      (description "RES SMD 22 OHM 1% 1/16W 0402")
      (fields (field (name "POWER") "63mW") (field (name "MANUFACTURER") "Yageo"))
      (libsource (lib "Resistance") (part "RC0402FR-0722RL"))
    )
    (comp (ref "R127")
      (value "RC0402FR-0722RL")
      (footprint "RESC1005X04N")
      (description "RES SMD 22 OHM 1% 1/16W 0402")
      (fields (field (name "POWER") "63mW") (field (name "MANUFACTURER") "Yageo"))
      (libsource (lib "Resistance") (part "RC0402FR-0722RL"))
    )
    (comp (ref "R128")
      (value "RC0402FR-0722RL")
      (footprint "RESC1005X04N")
      (description "RES SMD 22 OHM 1% 1/16W 0402")
      (fields (field (name "POWER") "63mW") (field (name "MANUFACTURER") "Yageo"))
      (libsource (lib "Resistance") (part "RC0402FR-0722RL"))
    )
    (comp (ref "R129")
      (value "RC0402FR-0722RL")
      (footprint "RESC1005X04N")
      (description "RES SMD 22 OHM 1% 1/16W 0402")
      (fields (field (name "POWER") "63mW") (field (name "MANUFACTURER") "Yageo"))
      (libsource (lib "Resistance") (part "RC0402FR-0722RL"))
    )
    (comp (ref "R130")
      (value "RC0402FR-0722RL")
      (footprint "RESC1005X04N")
      (description "RES SMD 22 OHM 1% 1/16W 0402")
      (fields (field (name "POWER") "63mW") (field (name "MANUFACTURER") "Yageo"))
      (libsource (lib "Resistance") (part "RC0402FR-0722RL"))
    )
    (comp (ref "R131")
      (value "RC0402FR-0722RL")
      (footprint "RESC1005X04N")
      (description "RES SMD 22 OHM 1% 1/16W 0402")
      (fields (field (name "POWER") "63mW") (field (name "MANUFACTURER") "Yageo"))
      (libsource (lib "Resistance") (part "RC0402FR-0722RL"))
    )
    (comp (ref "R132")
      (value "RC0402FR-0722RL")
      (footprint "RESC1005X04N")
      (description "RES SMD 22 OHM 1% 1/16W 0402")
      (fields (field (name "POWER") "63mW") (field (name "MANUFACTURER") "Yageo"))
      (libsource (lib "Resistance") (part "RC0402FR-0722RL"))
    )
    (comp (ref "R133")
      (value "RC0402FR-0722RL")
      (footprint "RESC1005X04N")
      (description "RES SMD 22 OHM 1% 1/16W 0402")
      (fields (field (name "POWER") "63mW") (field (name "MANUFACTURER") "Yageo"))
      (libsource (lib "Resistance") (part "RC0402FR-0722RL"))
    )
    (comp (ref "R134")
      (value "RC0402FR-0722RL")
      (footprint "RESC1005X04N")
      (description "RES SMD 22 OHM 1% 1/16W 0402")
      (fields (field (name "POWER") "63mW") (field (name "MANUFACTURER") "Yageo"))
      (libsource (lib "Resistance") (part "RC0402FR-0722RL"))
    )
    (comp (ref "R135")
      (value "RC0402FR-0722RL")
      (footprint "RESC1005X04N")
      (description "RES SMD 22 OHM 1% 1/16W 0402")
      (fields (field (name "POWER") "63mW") (field (name "MANUFACTURER") "Yageo"))
      (libsource (lib "Resistance") (part "RC0402FR-0722RL"))
    )
    (comp (ref "R136")
      (value "RC0402FR-0722RL")
      (footprint "RESC1005X04N")
      (description "RES SMD 22 OHM 1% 1/16W 0402")
      (fields (field (name "POWER") "63mW") (field (name "MANUFACTURER") "Yageo"))
      (libsource (lib "Resistance") (part "RC0402FR-0722RL"))
    )
    (comp (ref "R137")
      (value "RC0402FR-0722RL")
      (footprint "RESC1005X04N")
      (description "RES SMD 22 OHM 1% 1/16W 0402")
      (fields (field (name "POWER") "63mW") (field (name "MANUFACTURER") "Yageo"))
      (libsource (lib "Resistance") (part "RC0402FR-0722RL"))
    )
    (comp (ref "R138")
      (value "RC0402FR-0722RL")
      (footprint "RESC1005X04N")
      (description "RES SMD 22 OHM 1% 1/16W 0402")
      (fields (field (name "POWER") "63mW") (field (name "MANUFACTURER") "Yageo"))
      (libsource (lib "Resistance") (part "RC0402FR-0722RL"))
    )
    (comp (ref "R139")
      (value "RC0402FR-0722RL")
      (footprint "RESC1005X04N")
      (description "RES SMD 22 OHM 1% 1/16W 0402")
      (fields (field (name "POWER") "63mW") (field (name "MANUFACTURER") "Yageo"))
      (libsource (lib "Resistance") (part "RC0402FR-0722RL"))
    )
    (comp (ref "R140")
      (value "RC0402FR-0722RL")
      (footprint "RESC1005X04N")
      (description "RES SMD 22 OHM 1% 1/16W 0402")
      (fields (field (name "POWER") "63mW") (field (name "MANUFACTURER") "Yageo"))
      (libsource (lib "Resistance") (part "RC0402FR-0722RL"))
    )
    (comp (ref "R141")
      (value "RC0402FR-0722RL")
      (footprint "RESC1005X04N")
      (description "RES SMD 22 OHM 1% 1/16W 0402")
      (fields (field (name "POWER") "63mW") (field (name "MANUFACTURER") "Yageo"))
      (libsource (lib "Resistance") (part "RC0402FR-0722RL"))
    )
    (comp (ref "R142")
      (value "RC0402FR-0722RL")
      (footprint "RESC1005X04N")
      (description "RES SMD 22 OHM 1% 1/16W 0402")
      (fields (field (name "POWER") "63mW") (field (name "MANUFACTURER") "Yageo"))
      (libsource (lib "Resistance") (part "RC0402FR-0722RL"))
    )
    (comp (ref "R143")
      (value "RC0402FR-0722RL")
      (footprint "RESC1005X04N")
      (description "RES SMD 22 OHM 1% 1/16W 0402")
      (fields (field (name "POWER") "63mW") (field (name "MANUFACTURER") "Yageo"))
      (libsource (lib "Resistance") (part "RC0402FR-0722RL"))
    )
    (comp (ref "R144")
      (value "RC0402FR-0722RL")
      (footprint "RESC1005X04N")
      (description "RES SMD 22 OHM 1% 1/16W 0402")
      (fields (field (name "POWER") "63mW") (field (name "MANUFACTURER") "Yageo"))
      (libsource (lib "Resistance") (part "RC0402FR-0722RL"))
    )
    (comp (ref "R145")
      (value "RC0402FR-0722RL")
      (footprint "RESC1005X04N")
      (description "RES SMD 22 OHM 1% 1/16W 0402")
      (fields (field (name "POWER") "63mW") (field (name "MANUFACTURER") "Yageo"))
      (libsource (lib "Resistance") (part "RC0402FR-0722RL"))
    )
    (comp (ref "R146")
      (value "RC0402FR-0722RL")
      (footprint "RESC1005X04N")
      (description "RES SMD 22 OHM 1% 1/16W 0402")
      (fields (field (name "POWER") "63mW") (field (name "MANUFACTURER") "Yageo"))
      (libsource (lib "Resistance") (part "RC0402FR-0722RL"))
    )
    (comp (ref "R147")
      (value "RC0402FR-0722RL")
      (footprint "RESC1005X04N")
      (description "RES SMD 22 OHM 1% 1/16W 0402")
      (fields (field (name "POWER") "63mW") (field (name "MANUFACTURER") "Yageo"))
      (libsource (lib "Resistance") (part "RC0402FR-0722RL"))
    )
    (comp (ref "XM1")
      (value "DE0-nano")
      (footprint "DE0-NANO")
      (fields (field (name "MANUFACTURER") "TERASIC"))
      (libsource (lib "Divers_goldo") (part "DE0-nano"))
    )
  )
  (nets
    (net (code "1") (name "/FPGA_A2") (class "Default")
      (node (ref "R96") (pin "2") (pinfunction "2_2") (pintype "passive"))
      (node (ref "XM1") (pin "105") (pinfunction "GPIO_02_A2_105") (pintype "bidirectional"))
    )
    (net (code "2") (name "/FPGA_A3") (class "Default")
      (node (ref "R111") (pin "1") (pinfunction "1_1") (pintype "passive"))
      (node (ref "R18") (pin "1") (pinfunction "1_1") (pintype "passive"))
      (node (ref "XM1") (pin "106") (pinfunction "GPIO_03_A3_106") (pintype "bidirectional"))
    )
    (net (code "3") (name "/FPGA_A4") (class "Default")
      (node (ref "R98") (pin "2") (pinfunction "2_2") (pintype "passive"))
      (node (ref "XM1") (pin "109") (pinfunction "GPIO_06_A4_109") (pintype "bidirectional"))
    )
    (net (code "4") (name "/FPGA_A5") (class "Default")
      (node (ref "R99") (pin "2") (pinfunction "2_2") (pintype "passive"))
      (node (ref "XM1") (pin "113") (pinfunction "GPIO_08_A5_113") (pintype "bidirectional"))
    )
    (net (code "5") (name "/FPGA_A6") (class "Default")
      (node (ref "R115") (pin "1") (pinfunction "1_1") (pintype "passive"))
      (node (ref "XM1") (pin "116") (pinfunction "GPIO_011_A6_116") (pintype "bidirectional"))
    )
    (net (code "6") (name "/FPGA_A7") (class "Default")
      (node (ref "R5") (pin "1") (pinfunction "1_1") (pintype "passive"))
      (node (ref "XM1") (pin "119") (pinfunction "GPIO_014_A7_119") (pintype "bidirectional"))
    )
    (net (code "7") (name "/FPGA_A12") (class "Default")
      (node (ref "R107") (pin "2") (pinfunction "2_2") (pintype "passive"))
      (node (ref "XM1") (pin "137") (pinfunction "GPIO_030_A12_137") (pintype "bidirectional"))
    )
    (net (code "8") (name "/FPGA_A14") (class "Default")
      (node (ref "R125") (pin "2") (pinfunction "2_2") (pintype "passive"))
      (node (ref "XM1") (pin "305") (pinfunction "GPIO_20_A14_305") (pintype "bidirectional"))
    )
    (net (code "9") (name "/FPGA_ADC0") (class "Default")
      (node (ref "R147") (pin "1") (pinfunction "1_1") (pintype "passive"))
      (node (ref "XM1") (pin "324") (pinfunction "ANALOG_IN0_324") (pintype "input"))
    )
    (net (code "10") (name "/FPGA_ADC0_AIN") (class "Default")
      (node (ref "R147") (pin "2") (pinfunction "2_2") (pintype "passive"))
    )
    (net (code "11") (name "/FPGA_ADC0_GPIO") (class "Default")
      (node (ref "R130") (pin "1") (pinfunction "1_1") (pintype "passive"))
    )
    (net (code "12") (name "/FPGA_ADC1") (class "Default")
      (node (ref "R135") (pin "2") (pinfunction "2_2") (pintype "passive"))
      (node (ref "XM1") (pin "325") (pinfunction "ANALOG_IN1_325") (pintype "input"))
    )
    (net (code "13") (name "/FPGA_ADC1_AIN") (class "Default")
      (node (ref "R135") (pin "1") (pinfunction "1_1") (pintype "passive"))
    )
    (net (code "14") (name "/FPGA_ADC1_GPIO") (class "Default")
      (node (ref "R131") (pin "1") (pinfunction "1_1") (pintype "passive"))
    )
    (net (code "15") (name "/FPGA_ADC2") (class "Default")
      (node (ref "R146") (pin "1") (pinfunction "1_1") (pintype "passive"))
      (node (ref "XM1") (pin "322") (pinfunction "ANALOG_IN2_322") (pintype "input"))
    )
    (net (code "16") (name "/FPGA_ADC2_AIN") (class "Default")
      (node (ref "R146") (pin "2") (pinfunction "2_2") (pintype "passive"))
    )
    (net (code "17") (name "/FPGA_ADC2_GPIO") (class "Default")
      (node (ref "R129") (pin "1") (pinfunction "1_1") (pintype "passive"))
    )
    (net (code "18") (name "/FPGA_ADC3") (class "Default")
      (node (ref "R133") (pin "2") (pinfunction "2_2") (pintype "passive"))
      (node (ref "XM1") (pin "321") (pinfunction "ANALOG_IN3_321") (pintype "input"))
    )
    (net (code "19") (name "/FPGA_ADC3_AIN") (class "Default")
      (node (ref "R133") (pin "1") (pinfunction "1_1") (pintype "passive"))
    )
    (net (code "20") (name "/FPGA_ADC3_GPIO") (class "Default")
      (node (ref "R142") (pin "2") (pinfunction "2_2") (pintype "passive"))
    )
    (net (code "21") (name "/FPGA_ADC4") (class "Default")
      (node (ref "R134") (pin "2") (pinfunction "2_2") (pintype "passive"))
      (node (ref "XM1") (pin "323") (pinfunction "ANALOG_IN4_323") (pintype "input"))
    )
    (net (code "22") (name "/FPGA_ADC4_AIN") (class "Default")
      (node (ref "R134") (pin "1") (pinfunction "1_1") (pintype "passive"))
    )
    (net (code "23") (name "/FPGA_ADC4_GPIO") (class "Default")
      (node (ref "R143") (pin "2") (pinfunction "2_2") (pintype "passive"))
    )
    (net (code "24") (name "/FPGA_ADC5") (class "Default")
      (node (ref "R144") (pin "1") (pinfunction "1_1") (pintype "passive"))
      (node (ref "XM1") (pin "318") (pinfunction "ANALOG_IN5_318") (pintype "input"))
    )
    (net (code "25") (name "/FPGA_ADC5_AIN") (class "Default")
      (node (ref "R144") (pin "2") (pinfunction "2_2") (pintype "passive"))
    )
    (net (code "26") (name "/FPGA_ADC5_GPIO") (class "Default")
      (node (ref "R140") (pin "2") (pinfunction "2_2") (pintype "passive"))
    )
    (net (code "27") (name "/FPGA_ADC6") (class "Default")
      (node (ref "R132") (pin "2") (pinfunction "2_2") (pintype "passive"))
      (node (ref "XM1") (pin "319") (pinfunction "ANALOG_IN6_319") (pintype "input"))
    )
    (net (code "28") (name "/FPGA_ADC6_AIN") (class "Default")
      (node (ref "R132") (pin "1") (pinfunction "1_1") (pintype "passive"))
    )
    (net (code "29") (name "/FPGA_ADC6_GPIO") (class "Default")
      (node (ref "R128") (pin "1") (pinfunction "1_1") (pintype "passive"))
    )
    (net (code "30") (name "/FPGA_ADC7") (class "Default")
      (node (ref "R145") (pin "1") (pinfunction "1_1") (pintype "passive"))
      (node (ref "XM1") (pin "320") (pinfunction "ANALOG_IN7_320") (pintype "input"))
    )
    (net (code "31") (name "/FPGA_ADC7_AIN") (class "Default")
      (node (ref "R145") (pin "2") (pinfunction "2_2") (pintype "passive"))
    )
    (net (code "32") (name "/FPGA_ADC7_GPIO") (class "Default")
      (node (ref "R141") (pin "2") (pinfunction "2_2") (pintype "passive"))
    )
    (net (code "33") (name "/FPGA_B3") (class "Default")
      (node (ref "R97") (pin "2") (pinfunction "2_2") (pintype "passive"))
      (node (ref "XM1") (pin "107") (pinfunction "GPIO_04_B3_107") (pintype "bidirectional"))
    )
    (net (code "34") (name "/FPGA_B4") (class "Default")
      (node (ref "R112") (pin "1") (pinfunction "1_1") (pintype "passive"))
      (node (ref "R9") (pin "1") (pinfunction "1_1") (pintype "passive"))
      (node (ref "XM1") (pin "108") (pinfunction "GPIO_05_B4_108") (pintype "bidirectional"))
    )
    (net (code "35") (name "/FPGA_B5") (class "Default")
      (node (ref "R113") (pin "1") (pinfunction "1_1") (pintype "passive"))
      (node (ref "XM1") (pin "110") (pinfunction "GPIO_07_B5_110") (pintype "bidirectional"))
    )
    (net (code "36") (name "/FPGA_B6") (class "Default")
      (node (ref "R100") (pin "2") (pinfunction "2_2") (pintype "passive"))
      (node (ref "XM1") (pin "115") (pinfunction "GPIO_010_B6_115") (pintype "bidirectional"))
    )
    (net (code "37") (name "/FPGA_B7") (class "Default")
      (node (ref "R101") (pin "2") (pinfunction "2_2") (pintype "passive"))
      (node (ref "XM1") (pin "117") (pinfunction "GPIO_012_B7_117") (pintype "bidirectional"))
    )
    (net (code "38") (name "/FPGA_B11") (class "Default")
      (node (ref "R121") (pin "1") (pinfunction "1_1") (pintype "passive"))
      (node (ref "XM1") (pin "136") (pinfunction "GPIO_029_B11_136") (pintype "bidirectional"))
    )
    (net (code "39") (name "/FPGA_B12") (class "Default")
      (node (ref "R123") (pin "1") (pinfunction "1_1") (pintype "passive"))
      (node (ref "XM1") (pin "140") (pinfunction "GPIO_033_B12_140") (pintype "bidirectional"))
    )
    (net (code "40") (name "/FPGA_B16") (class "Default")
      (node (ref "R138") (pin "1") (pinfunction "1_1") (pintype "passive"))
      (node (ref "XM1") (pin "306") (pinfunction "GPIO_21_B16_306") (pintype "bidirectional"))
    )
    (net (code "41") (name "/FPGA_C3") (class "Default")
      (node (ref "R110") (pin "1") (pinfunction "1_1") (pintype "passive"))
      (node (ref "XM1") (pin "104") (pinfunction "GPIO_01_C3_104") (pintype "bidirectional"))
    )
    (net (code "42") (name "/FPGA_C6") (class "Default")
      (node (ref "R4") (pin "1") (pinfunction "1_1") (pintype "passive"))
      (node (ref "XM1") (pin "120") (pinfunction "GPIO_015_C6_120") (pintype "bidirectional"))
    )
    (net (code "43") (name "/FPGA_C8") (class "Default")
      (node (ref "R102") (pin "2") (pinfunction "2_2") (pintype "passive"))
      (node (ref "XM1") (pin "121") (pinfunction "GPIO_016_C8_121") (pintype "bidirectional"))
    )
    (net (code "44") (name "/FPGA_C9") (class "Default")
      (node (ref "R1") (pin "1") (pinfunction "1_1") (pintype "passive"))
      (node (ref "XM1") (pin "131") (pinfunction "GPIO_024_C9_131") (pintype "bidirectional"))
    )
    (net (code "45") (name "/FPGA_C11") (class "Default")
      (node (ref "R106") (pin "2") (pinfunction "2_2") (pintype "passive"))
      (node (ref "XM1") (pin "135") (pinfunction "GPIO_028_C11_135") (pintype "bidirectional"))
    )
    (net (code "46") (name "/FPGA_C14") (class "Default")
      (node (ref "R126") (pin "2") (pinfunction "2_2") (pintype "passive"))
      (node (ref "XM1") (pin "307") (pinfunction "GPIO_22_C14_307") (pintype "bidirectional"))
    )
    (net (code "47") (name "/FPGA_C15") (class "Default")
      (node (ref "R127") (pin "2") (pinfunction "2_2") (pintype "passive"))
      (node (ref "XM1") (pin "309") (pinfunction "GPIO_24_C15_309") (pintype "bidirectional"))
    )
    (net (code "48") (name "/FPGA_C16") (class "Default")
      (node (ref "R139") (pin "1") (pinfunction "1_1") (pintype "passive"))
      (node (ref "XM1") (pin "308") (pinfunction "GPIO_23_C16_308") (pintype "bidirectional"))
    )
    (net (code "49") (name "/FPGA_D3") (class "Default")
      (node (ref "R109") (pin "1") (pinfunction "1_1") (pintype "passive"))
      (node (ref "XM1") (pin "102") (pinfunction "GPIO_00_D3_102") (pintype "bidirectional"))
    )
    (net (code "50") (name "/FPGA_D5") (class "Default")
      (node (ref "R114") (pin "1") (pinfunction "1_1") (pintype "passive"))
      (node (ref "XM1") (pin "114") (pinfunction "GPIO_09_D5_114") (pintype "bidirectional"))
    )
    (net (code "51") (name "/FPGA_D6") (class "Default")
      (node (ref "R116") (pin "1") (pinfunction "1_1") (pintype "passive"))
      (node (ref "XM1") (pin "118") (pinfunction "GPIO_013_D6_118") (pintype "bidirectional"))
    )
    (net (code "52") (name "/FPGA_D8") (class "Default")
      (node (ref "R118") (pin "1") (pinfunction "1_1") (pintype "passive"))
      (node (ref "XM1") (pin "124") (pinfunction "GPIO_019_D8_124") (pintype "bidirectional"))
    )
    (net (code "53") (name "/FPGA_D9") (class "Default")
      (node (ref "R16") (pin "1") (pinfunction "1_1") (pintype "passive"))
      (node (ref "XM1") (pin "132") (pinfunction "GPIO_025_D9_132") (pintype "bidirectional"))
    )
    (net (code "54") (name "/FPGA_D11") (class "Default")
      (node (ref "R122") (pin "1") (pinfunction "1_1") (pintype "passive"))
      (node (ref "XM1") (pin "138") (pinfunction "GPIO_031_D11_138") (pintype "bidirectional"))
    )
    (net (code "55") (name "/FPGA_D12") (class "Default")
      (node (ref "R108") (pin "2") (pinfunction "2_2") (pintype "passive"))
      (node (ref "XM1") (pin "139") (pinfunction "GPIO_032_D12_139") (pintype "bidirectional"))
    )
    (net (code "56") (name "/FPGA_D14") (class "Default")
      (node (ref "R141") (pin "1") (pinfunction "1_1") (pintype "passive"))
      (node (ref "XM1") (pin "312") (pinfunction "GPIO_27_D14_312") (pintype "bidirectional"))
    )
    (net (code "57") (name "/FPGA_D15") (class "Default")
      (node (ref "R128") (pin "2") (pinfunction "2_2") (pintype "passive"))
      (node (ref "XM1") (pin "311") (pinfunction "GPIO_26_D15_311") (pintype "bidirectional"))
    )
    (net (code "58") (name "/FPGA_D16") (class "Default")
      (node (ref "R140") (pin "1") (pinfunction "1_1") (pintype "passive"))
      (node (ref "XM1") (pin "310") (pinfunction "GPIO_25_D16_310") (pintype "bidirectional"))
    )
    (net (code "59") (name "/FPGA_E6") (class "Default")
      (node (ref "R117") (pin "1") (pinfunction "1_1") (pintype "passive"))
      (node (ref "XM1") (pin "122") (pinfunction "GPIO_017_E6_122") (pintype "bidirectional"))
    )
    (net (code "60") (name "/FPGA_E7") (class "Default")
      (node (ref "R103") (pin "2") (pinfunction "2_2") (pintype "passive"))
      (node (ref "XM1") (pin "123") (pinfunction "GPIO_018_E7_123") (pintype "bidirectional"))
    )
    (net (code "61") (name "/FPGA_E8") (class "Default")
      (node (ref "R104") (pin "2") (pinfunction "2_2") (pintype "passive"))
      (node (ref "XM1") (pin "125") (pinfunction "GPIO_020_E8_125") (pintype "bidirectional"))
    )
    (net (code "62") (name "/FPGA_E9") (class "Default")
      (node (ref "R2") (pin "1") (pinfunction "1_1") (pintype "passive"))
      (node (ref "XM1") (pin "128") (pinfunction "GPIO_023_E9_128") (pintype "bidirectional"))
    )
    (net (code "63") (name "/FPGA_E10") (class "Default")
      (node (ref "R120") (pin "1") (pinfunction "1_1") (pintype "passive"))
      (node (ref "XM1") (pin "134") (pinfunction "GPIO_027_E10_134") (pintype "bidirectional"))
    )
    (net (code "64") (name "/FPGA_E11") (class "Default")
      (node (ref "R105") (pin "2") (pinfunction "2_2") (pintype "passive"))
      (node (ref "XM1") (pin "133") (pinfunction "GPIO_026_E11_133") (pintype "bidirectional"))
    )
    (net (code "65") (name "/FPGA_E15") (class "Default")
      (node (ref "R136") (pin "1") (pinfunction "1_1") (pintype "passive"))
      (node (ref "XM1") (pin "302") (pinfunction "GPIO_2_IN0_E15_302") (pintype "input"))
    )
    (net (code "66") (name "/FPGA_F8") (class "Default")
      (node (ref "R119") (pin "1") (pinfunction "1_1") (pintype "passive"))
      (node (ref "XM1") (pin "126") (pinfunction "GPIO_021_F8_126") (pintype "bidirectional"))
    )
    (net (code "67") (name "/FPGA_F9") (class "Default")
      (node (ref "R17") (pin "1") (pinfunction "1_1") (pintype "passive"))
      (node (ref "XM1") (pin "127") (pinfunction "GPIO_022_F9_127") (pintype "bidirectional"))
    )
    (net (code "68") (name "/FPGA_F13") (class "Default")
      (node (ref "R81") (pin "2") (pinfunction "2_2") (pintype "passive"))
      (node (ref "XM1") (pin "202") (pinfunction "GPIO_10_F13_202") (pintype "bidirectional"))
    )
    (net (code "69") (name "/FPGA_F14") (class "Default")
      (node (ref "R130") (pin "2") (pinfunction "2_2") (pintype "passive"))
      (node (ref "XM1") (pin "315") (pinfunction "GPIO_210_F14_315") (pintype "bidirectional"))
    )
    (net (code "70") (name "/FPGA_F15") (class "Default")
      (node (ref "R129") (pin "2") (pinfunction "2_2") (pintype "passive"))
      (node (ref "XM1") (pin "313") (pinfunction "GPIO_28_F15_313") (pintype "bidirectional"))
    )
    (net (code "71") (name "/FPGA_F16") (class "Default")
      (node (ref "R142") (pin "1") (pinfunction "1_1") (pintype "passive"))
      (node (ref "XM1") (pin "314") (pinfunction "GPIO_29_F16_314") (pintype "bidirectional"))
    )
    (net (code "72") (name "/FPGA_G15") (class "Default")
      (node (ref "R131") (pin "2") (pinfunction "2_2") (pintype "passive"))
      (node (ref "XM1") (pin "317") (pinfunction "GPIO_212_G15_317") (pintype "bidirectional"))
    )
    (net (code "73") (name "/FPGA_G16") (class "Default")
      (node (ref "R143") (pin "1") (pinfunction "1_1") (pintype "passive"))
      (node (ref "XM1") (pin "316") (pinfunction "GPIO_211_G16_316") (pintype "bidirectional"))
    )
    (net (code "74") (name "/FPGA_I2CS_SCL") (class "Default")
      (node (ref "R106") (pin "1") (pinfunction "1_1") (pintype "passive"))
    )
    (net (code "75") (name "/FPGA_I2CS_SDA") (class "Default")
      (node (ref "R121") (pin "2") (pinfunction "2_2") (pintype "passive"))
    )
    (net (code "76") (name "/FPGA_IN_A8") (class "Default")
      (node (ref "R20") (pin "1") (pinfunction "1_1") (pintype "passive"))
      (node (ref "XM1") (pin "101") (pinfunction "GPIO_0_IN0_A8_101") (pintype "input"))
    )
    (net (code "77") (name "/FPGA_IN_B8") (class "Default")
      (node (ref "R19") (pin "1") (pinfunction "1_1") (pintype "passive"))
      (node (ref "R95") (pin "2") (pinfunction "2_2") (pintype "passive"))
      (node (ref "XM1") (pin "103") (pinfunction "GPIO_0_IN1_B8_103") (pintype "input"))
    )
    (net (code "78") (name "/FPGA_IN_E16") (class "Default")
      (node (ref "R124") (pin "2") (pinfunction "2_2") (pintype "passive"))
      (node (ref "XM1") (pin "303") (pinfunction "GPIO_2_IN1_E16_303") (pintype "input"))
    )
    (net (code "79") (name "/FPGA_IN_R9") (class "Default")
      (node (ref "R93") (pin "1") (pinfunction "1_1") (pintype "passive"))
      (node (ref "XM1") (pin "203") (pinfunction "GPIO_1_IN1_R9_203") (pintype "input"))
    )
    (net (code "80") (name "/FPGA_IN_T9") (class "Default")
      (node (ref "R94") (pin "1") (pinfunction "1_1") (pintype "passive"))
      (node (ref "XM1") (pin "201") (pinfunction "GPIO_1_IN0_T9_201") (pintype "input"))
    )
    (net (code "81") (name "/FPGA_J13") (class "Default")
      (node (ref "R50") (pin "1") (pinfunction "1_1") (pintype "passive"))
      (node (ref "XM1") (pin "239") (pinfunction "GPIO_132_J13_239") (pintype "bidirectional"))
    )
    (net (code "82") (name "/FPGA_J14") (class "Default")
      (node (ref "R37") (pin "2") (pinfunction "2_2") (pintype "passive"))
      (node (ref "XM1") (pin "240") (pinfunction "GPIO_133_J14_240") (pintype "bidirectional"))
    )
    (net (code "83") (name "/FPGA_J16") (class "Default")
      (node (ref "R49") (pin "1") (pinfunction "1_1") (pintype "passive"))
      (node (ref "XM1") (pin "237") (pinfunction "GPIO_130_J16_237") (pintype "bidirectional"))
    )
    (net (code "84") (name "/FPGA_K15") (class "Default")
      (node (ref "R36") (pin "2") (pinfunction "2_2") (pintype "passive"))
      (node (ref "XM1") (pin "238") (pinfunction "GPIO_131_K15_238") (pintype "bidirectional"))
    )
    (net (code "85") (name "/FPGA_K16") (class "Default")
      (node (ref "R28") (pin "2") (pinfunction "2_2") (pintype "passive"))
      (node (ref "XM1") (pin "222") (pinfunction "GPIO_117_K16_222") (pintype "bidirectional"))
    )
    (net (code "86") (name "/FPGA_L13") (class "Default")
      (node (ref "R35") (pin "2") (pinfunction "2_2") (pintype "passive"))
      (node (ref "XM1") (pin "236") (pinfunction "GPIO_129_L13_236") (pintype "bidirectional"))
    )
    (net (code "87") (name "/FPGA_L14") (class "Default")
      (node (ref "R82") (pin "1") (pinfunction "1_1") (pintype "passive"))
      (node (ref "XM1") (pin "233") (pinfunction "GPIO_126_L14_233") (pintype "bidirectional"))
    )
    (net (code "88") (name "/FPGA_L15") (class "Default")
      (node (ref "R29") (pin "2") (pinfunction "2_2") (pintype "passive"))
      (node (ref "XM1") (pin "224") (pinfunction "GPIO_119_L15_224") (pintype "bidirectional"))
    )
    (net (code "89") (name "/FPGA_L16") (class "Default")
      (node (ref "R85") (pin "1") (pinfunction "1_1") (pintype "passive"))
      (node (ref "XM1") (pin "221") (pinfunction "GPIO_116_L16_221") (pintype "bidirectional"))
    )
    (net (code "90") (name "/FPGA_M10") (class "Default")
      (node (ref "R48") (pin "1") (pinfunction "1_1") (pintype "passive"))
      (node (ref "XM1") (pin "235") (pinfunction "GPIO_128_M10_235") (pintype "bidirectional"))
    )
    (net (code "91") (name "/FPGA_M16") (class "Default")
      (node (ref "R137") (pin "1") (pinfunction "1_1") (pintype "passive"))
      (node (ref "XM1") (pin "304") (pinfunction "GPIO_2_IN2_M16_304") (pintype "input"))
    )
    (net (code "92") (name "/FPGA_N9") (class "Default")
      (node (ref "R86") (pin "1") (pinfunction "1_1") (pintype "passive"))
      (node (ref "XM1") (pin "219") (pinfunction "GPIO_114_N9_219") (pintype "bidirectional"))
    )
    (net (code "93") (name "/FPGA_N11") (class "Default")
      (node (ref "R27") (pin "2") (pinfunction "2_2") (pintype "passive"))
      (node (ref "XM1") (pin "220") (pinfunction "GPIO_115_N11_220") (pintype "bidirectional"))
    )
    (net (code "94") (name "/FPGA_N12") (class "Default")
      (node (ref "R87") (pin "1") (pinfunction "1_1") (pintype "passive"))
      (node (ref "XM1") (pin "217") (pinfunction "GPIO_112_N12_217") (pintype "bidirectional"))
    )
    (net (code "95") (name "/FPGA_N14") (class "Default")
      (node (ref "R34") (pin "2") (pinfunction "2_2") (pintype "passive"))
      (node (ref "XM1") (pin "234") (pinfunction "GPIO_127_N14_234") (pintype "bidirectional"))
    )
    (net (code "96") (name "/FPGA_N15") (class "Default")
      (node (ref "R83") (pin "1") (pinfunction "1_1") (pintype "passive"))
      (node (ref "XM1") (pin "231") (pinfunction "GPIO_124_N15_231") (pintype "bidirectional"))
    )
    (net (code "97") (name "/FPGA_N16") (class "Default")
      (node (ref "R46") (pin "1") (pinfunction "1_1") (pintype "passive"))
      (node (ref "R73") (pin "2") (pinfunction "2_2") (pintype "passive"))
      (node (ref "XM1") (pin "228") (pinfunction "GPIO_123_N16_228") (pintype "bidirectional"))
    )
    (net (code "98") (name "/FPGA_P9") (class "Default")
      (node (ref "R74") (pin "2") (pinfunction "2_2") (pintype "passive"))
      (node (ref "XM1") (pin "218") (pinfunction "GPIO_113_P9_218") (pintype "bidirectional"))
    )
    (net (code "99") (name "/FPGA_P11") (class "Default")
      (node (ref "R88") (pin "1") (pinfunction "1_1") (pintype "passive"))
      (node (ref "XM1") (pin "215") (pinfunction "GPIO_110_P11_215") (pintype "bidirectional"))
    )
    (net (code "100") (name "/FPGA_P14") (class "Default")
      (node (ref "R33") (pin "2") (pinfunction "2_2") (pintype "passive"))
      (node (ref "XM1") (pin "232") (pinfunction "GPIO_125_P14_232") (pintype "bidirectional"))
    )
    (net (code "101") (name "/FPGA_P15") (class "Default")
      (node (ref "R31") (pin "2") (pinfunction "2_2") (pintype "passive"))
      (node (ref "R84") (pin "1") (pinfunction "1_1") (pintype "passive"))
      (node (ref "XM1") (pin "225") (pinfunction "GPIO_120_P15_225") (pintype "bidirectional"))
    )
    (net (code "102") (name "/FPGA_P16") (class "Default")
      (node (ref "R45") (pin "1") (pinfunction "1_1") (pintype "passive"))
      (node (ref "XM1") (pin "226") (pinfunction "GPIO_121_P16_226") (pintype "bidirectional"))
    )
    (net (code "103") (name "/FPGA_PWM_0") (class "Default")
      (node (ref "R122") (pin "2") (pinfunction "2_2") (pintype "passive"))
    )
    (net (code "104") (name "/FPGA_PWM_1") (class "Default")
      (node (ref "R107") (pin "1") (pinfunction "1_1") (pintype "passive"))
    )
    (net (code "105") (name "/FPGA_PWM_2") (class "Default")
      (node (ref "R123") (pin "2") (pinfunction "2_2") (pintype "passive"))
    )
    (net (code "106") (name "/FPGA_PWM_3") (class "Default")
      (node (ref "R108") (pin "1") (pinfunction "1_1") (pintype "passive"))
    )
    (net (code "107") (name "/FPGA_PWM_4") (class "Default")
      (node (ref "R138") (pin "2") (pinfunction "2_2") (pintype "passive"))
    )
    (net (code "108") (name "/FPGA_PWM_5") (class "Default")
      (node (ref "R126") (pin "1") (pinfunction "1_1") (pintype "passive"))
    )
    (net (code "109") (name "/FPGA_PWM_6") (class "Default")
      (node (ref "R139") (pin "2") (pinfunction "2_2") (pintype "passive"))
    )
    (net (code "110") (name "/FPGA_PWM_7") (class "Default")
      (node (ref "R127") (pin "1") (pinfunction "1_1") (pintype "passive"))
    )
    (net (code "111") (name "/FPGA_PWM_8") (class "Default")
      (node (ref "R86") (pin "2") (pinfunction "2_2") (pintype "passive"))
    )
    (net (code "112") (name "/FPGA_PWM_9") (class "Default")
      (node (ref "R87") (pin "2") (pinfunction "2_2") (pintype "passive"))
    )
    (net (code "113") (name "/FPGA_PWM_10") (class "Default")
      (node (ref "R74") (pin "1") (pinfunction "1_1") (pintype "passive"))
    )
    (net (code "114") (name "/FPGA_PWM_11") (class "Default")
      (node (ref "R88") (pin "2") (pinfunction "2_2") (pintype "passive"))
    )
    (net (code "115") (name "/FPGA_R10") (class "Default")
      (node (ref "R75") (pin "2") (pinfunction "2_2") (pintype "passive"))
      (node (ref "XM1") (pin "216") (pinfunction "GPIO_111_R10_216") (pintype "bidirectional"))
    )
    (net (code "116") (name "/FPGA_R11") (class "Default")
      (node (ref "R76") (pin "2") (pinfunction "2_2") (pintype "passive"))
      (node (ref "XM1") (pin "214") (pinfunction "GPIO_19_R11_214") (pintype "bidirectional"))
    )
    (net (code "117") (name "/FPGA_R12") (class "Default")
      (node (ref "R90") (pin "1") (pinfunction "1_1") (pintype "passive"))
      (node (ref "XM1") (pin "209") (pinfunction "GPIO_16_R12_209") (pintype "bidirectional"))
    )
    (net (code "118") (name "/FPGA_R13") (class "Default")
      (node (ref "R91") (pin "1") (pinfunction "1_1") (pintype "passive"))
      (node (ref "XM1") (pin "207") (pinfunction "GPIO_14_R13_207") (pintype "bidirectional"))
    )
    (net (code "119") (name "/FPGA_R14") (class "Default")
      (node (ref "R32") (pin "2") (pinfunction "2_2") (pintype "passive"))
      (node (ref "XM1") (pin "227") (pinfunction "GPIO_122_R14_227") (pintype "bidirectional"))
    )
    (net (code "120") (name "/FPGA_R16") (class "Default")
      (node (ref "R44") (pin "1") (pinfunction "1_1") (pintype "passive"))
      (node (ref "XM1") (pin "223") (pinfunction "GPIO_118_R16_223") (pintype "bidirectional"))
    )
    (net (code "121") (name "/FPGA_SPIM1_MISO") (class "Default")
      (node (ref "R91") (pin "2") (pinfunction "2_2") (pintype "passive"))
    )
    (net (code "122") (name "/FPGA_SPIM1_MOSI") (class "Default")
      (node (ref "R79") (pin "1") (pinfunction "1_1") (pintype "passive"))
    )
    (net (code "123") (name "/FPGA_SPIM1_NSS") (class "Default")
      (node (ref "R92") (pin "2") (pinfunction "2_2") (pintype "passive"))
    )
    (net (code "124") (name "/FPGA_SPIM1_SCK") (class "Default")
      (node (ref "R78") (pin "1") (pinfunction "1_1") (pintype "passive"))
    )
    (net (code "125") (name "/FPGA_SPIM2_MISO") (class "Default")
      (node (ref "R76") (pin "1") (pinfunction "1_1") (pintype "passive"))
    )
    (net (code "126") (name "/FPGA_SPIM2_MOSI") (class "Default")
      (node (ref "R77") (pin "1") (pinfunction "1_1") (pintype "passive"))
    )
    (net (code "127") (name "/FPGA_SPIM2_NSS") (class "Default")
      (node (ref "R90") (pin "2") (pinfunction "2_2") (pintype "passive"))
    )
    (net (code "128") (name "/FPGA_SPIM2_SCK") (class "Default")
      (node (ref "R89") (pin "2") (pinfunction "2_2") (pintype "passive"))
    )
    (net (code "129") (name "/FPGA_STP0_DIR") (class "Default")
      (node (ref "R116") (pin "2") (pinfunction "2_2") (pintype "passive"))
    )
    (net (code "130") (name "/FPGA_STP0_PWM") (class "Default")
      (node (ref "R115") (pin "2") (pinfunction "2_2") (pintype "passive"))
    )
    (net (code "131") (name "/FPGA_STP1_DIR") (class "Default")
      (node (ref "R101") (pin "1") (pinfunction "1_1") (pintype "passive"))
    )
    (net (code "132") (name "/FPGA_STP1_PWM") (class "Default")
      (node (ref "R100") (pin "1") (pinfunction "1_1") (pintype "passive"))
    )
    (net (code "133") (name "/FPGA_STP2_DIR") (class "Default")
      (node (ref "R114") (pin "2") (pinfunction "2_2") (pintype "passive"))
    )
    (net (code "134") (name "/FPGA_STP2_PWM") (class "Default")
      (node (ref "R99") (pin "1") (pinfunction "1_1") (pintype "passive"))
    )
    (net (code "135") (name "/FPGA_STP3_DIR") (class "Default")
      (node (ref "R113") (pin "2") (pinfunction "2_2") (pintype "passive"))
    )
    (net (code "136") (name "/FPGA_STP3_PWM") (class "Default")
      (node (ref "R98") (pin "1") (pinfunction "1_1") (pintype "passive"))
    )
    (net (code "137") (name "/FPGA_STP4_DIR") (class "Default")
      (node (ref "R97") (pin "1") (pinfunction "1_1") (pintype "passive"))
    )
    (net (code "138") (name "/FPGA_STP4_PWM") (class "Default")
      (node (ref "R96") (pin "1") (pinfunction "1_1") (pintype "passive"))
    )
    (net (code "139") (name "/FPGA_STP5_DIR") (class "Default")
      (node (ref "R110") (pin "2") (pinfunction "2_2") (pintype "passive"))
    )
    (net (code "140") (name "/FPGA_STP5_PWM") (class "Default")
      (node (ref "R109") (pin "2") (pinfunction "2_2") (pintype "passive"))
    )
    (net (code "141") (name "/FPGA_T10") (class "Default")
      (node (ref "R89") (pin "1") (pinfunction "1_1") (pintype "passive"))
      (node (ref "XM1") (pin "213") (pinfunction "GPIO_18_T10_213") (pintype "bidirectional"))
    )
    (net (code "142") (name "/FPGA_T11") (class "Default")
      (node (ref "R77") (pin "2") (pinfunction "2_2") (pintype "passive"))
      (node (ref "XM1") (pin "210") (pinfunction "GPIO_17_T11_210") (pintype "bidirectional"))
    )
    (net (code "143") (name "/FPGA_T12") (class "Default")
      (node (ref "R78") (pin "2") (pinfunction "2_2") (pintype "passive"))
      (node (ref "XM1") (pin "208") (pinfunction "GPIO_15_T12_208") (pintype "bidirectional"))
    )
    (net (code "144") (name "/FPGA_T13") (class "Default")
      (node (ref "R79") (pin "2") (pinfunction "2_2") (pintype "passive"))
      (node (ref "XM1") (pin "206") (pinfunction "GPIO_13_T13_206") (pintype "bidirectional"))
    )
    (net (code "145") (name "/FPGA_T14") (class "Default")
      (node (ref "R92") (pin "1") (pinfunction "1_1") (pintype "passive"))
      (node (ref "XM1") (pin "205") (pinfunction "GPIO_12_T14_205") (pintype "bidirectional"))
    )
    (net (code "146") (name "/FPGA_T15") (class "Default")
      (node (ref "R80") (pin "2") (pinfunction "2_2") (pintype "passive"))
      (node (ref "XM1") (pin "204") (pinfunction "GPIO_11_T15_204") (pintype "bidirectional"))
    )
    (net (code "147") (name "/FPGA_UART1_RX") (class "Default")
      (node (ref "R102") (pin "1") (pinfunction "1_1") (pintype "passive"))
    )
    (net (code "148") (name "/FPGA_UART1_TX") (class "Default")
      (node (ref "R117") (pin "2") (pinfunction "2_2") (pintype "passive"))
    )
    (net (code "149") (name "/FPGA_UART2_RX") (class "Default")
      (node (ref "R103") (pin "1") (pinfunction "1_1") (pintype "passive"))
    )
    (net (code "150") (name "/FPGA_UART2_TX") (class "Default")
      (node (ref "R118") (pin "2") (pinfunction "2_2") (pintype "passive"))
    )
    (net (code "151") (name "/FPGA_UART3_RX") (class "Default")
      (node (ref "R104") (pin "1") (pinfunction "1_1") (pintype "passive"))
    )
    (net (code "152") (name "/FPGA_UART3_TX") (class "Default")
      (node (ref "R119") (pin "2") (pinfunction "2_2") (pintype "passive"))
    )
    (net (code "153") (name "/FPGA_UART4_RX") (class "Default")
      (node (ref "R105") (pin "1") (pinfunction "1_1") (pintype "passive"))
    )
    (net (code "154") (name "/FPGA_UART4_TX") (class "Default")
      (node (ref "R120") (pin "2") (pinfunction "2_2") (pintype "passive"))
    )
    (net (code "155") (name "/FPGA_US1_ECHO") (class "Default")
      (node (ref "R85") (pin "2") (pinfunction "2_2") (pintype "passive"))
    )
    (net (code "156") (name "/FPGA_US1_TRIG") (class "Default")
      (node (ref "R83") (pin "2") (pinfunction "2_2") (pintype "passive"))
    )
    (net (code "157") (name "/FPGA_US2_ECHO") (class "Default")
      (node (ref "R125") (pin "1") (pinfunction "1_1") (pintype "passive"))
    )
    (net (code "158") (name "/FPGA_US2_TRIG") (class "Default")
      (node (ref "R137") (pin "2") (pinfunction "2_2") (pintype "passive"))
    )
    (net (code "159") (name "/FPGA_US3_ECHO") (class "Default")
      (node (ref "R124") (pin "1") (pinfunction "1_1") (pintype "passive"))
    )
    (net (code "160") (name "/FPGA_US3_TRIG") (class "Default")
      (node (ref "R136") (pin "2") (pinfunction "2_2") (pintype "passive"))
    )
    (net (code "161") (name "/FPGA_US4_ECHO") (class "Default")
      (node (ref "R94") (pin "2") (pinfunction "2_2") (pintype "passive"))
    )
    (net (code "162") (name "/FPGA_US4_TRIG") (class "Default")
      (node (ref "R81") (pin "1") (pinfunction "1_1") (pintype "passive"))
    )
    (net (code "163") (name "/FPGA_US5_ECHO") (class "Default")
      (node (ref "R93") (pin "2") (pinfunction "2_2") (pintype "passive"))
    )
    (net (code "164") (name "/FPGA_US5_TRIG") (class "Default")
      (node (ref "R80") (pin "1") (pinfunction "1_1") (pintype "passive"))
    )
    (net (code "165") (name "/MAXON1_DIR") (class "Default")
      (node (ref "R65") (pin "2") (pinfunction "2_2") (pintype "passive"))
    )
    (net (code "166") (name "/MAXON1_PWM") (class "Default")
      (node (ref "R64") (pin "1") (pinfunction "1_1") (pintype "passive"))
    )
    (net (code "167") (name "/MAXON2_DIR") (class "Default")
      (node (ref "R57") (pin "1") (pinfunction "1_1") (pintype "passive"))
    )
    (net (code "168") (name "/MAXON2_PWM") (class "Default")
      (node (ref "R58") (pin "1") (pinfunction "1_1") (pintype "passive"))
    )
    (net (code "169") (name "/MAXON_EN") (class "Default")
      (node (ref "R56") (pin "2") (pinfunction "2_2") (pintype "passive"))
    )
    (net (code "170") (name "/NUCLEO_ADC1.8_AIN") (class "Default")
      (node (ref "R12") (pin "2") (pinfunction "2_2") (pintype "passive"))
    )
    (net (code "171") (name "/NUCLEO_ADC1.8_GPIO") (class "Default")
      (node (ref "R22") (pin "1") (pinfunction "1_1") (pintype "passive"))
    )
    (net (code "172") (name "/NUCLEO_ADC1.9_AIN") (class "Default")
      (node (ref "R13") (pin "2") (pinfunction "2_2") (pintype "passive"))
    )
    (net (code "173") (name "/NUCLEO_ADC1.9_GPIO") (class "Default")
      (node (ref "R23") (pin "1") (pinfunction "1_1") (pintype "passive"))
    )
    (net (code "174") (name "/NUCLEO_CAN_RX") (class "Default")
      (node (ref "R43") (pin "1") (pinfunction "1_1") (pintype "passive"))
    )
    (net (code "175") (name "/NUCLEO_CAN_TX") (class "Default")
      (node (ref "R42") (pin "1") (pinfunction "1_1") (pintype "passive"))
    )
    (net (code "176") (name "/NUCLEO_DYNA_DIR") (class "Default")
      (node (ref "R41") (pin "1") (pinfunction "1_1") (pintype "passive"))
    )
    (net (code "177") (name "/NUCLEO_DYNA_RX") (class "Default")
      (node (ref "R38") (pin "2") (pinfunction "2_2") (pintype "passive"))
    )
    (net (code "178") (name "/NUCLEO_DYNA_TX") (class "Default")
      (node (ref "R51") (pin "1") (pinfunction "1_1") (pintype "passive"))
    )
    (net (code "179") (name "/NUCLEO_GPIO_PB0") (class "Default")
      (node (ref "R21") (pin "1") (pinfunction "1_1") (pintype "passive"))
    )
    (net (code "180") (name "/NUCLEO_GPIO_PC6") (class "Default")
      (node (ref "R40") (pin "1") (pinfunction "1_1") (pintype "passive"))
    )
    (net (code "181") (name "/NUCLEO_GPIO_PC8") (class "Default")
      (node (ref "R39") (pin "1") (pinfunction "1_1") (pintype "passive"))
    )
    (net (code "182") (name "/NUCLEO_GPIO_PC9") (class "Default")
      (node (ref "R24") (pin "2") (pinfunction "2_2") (pintype "passive"))
    )
    (net (code "183") (name "/NUCLEO_GPIO_PC13") (class "Default")
      (node (ref "R7") (pin "1") (pinfunction "1_1") (pintype "passive"))
    )
    (net (code "184") (name "/NUCLEO_GPIO_PC14") (class "Default")
      (node (ref "R8") (pin "1") (pinfunction "1_1") (pintype "passive"))
    )
    (net (code "185") (name "/NUCLEO_I2C1_SCL") (class "Default")
      (node (ref "R25") (pin "2") (pinfunction "2_2") (pintype "passive"))
    )
    (net (code "186") (name "/NUCLEO_I2C1_SDA") (class "Default")
      (node (ref "R26") (pin "2") (pinfunction "2_2") (pintype "passive"))
    )
    (net (code "187") (name "/NUCLEO_I2C2_SCL") (class "Default")
      (node (ref "R11") (pin "2") (pinfunction "2_2") (pintype "passive"))
    )
    (net (code "188") (name "/NUCLEO_I2C2_SDA") (class "Default")
      (node (ref "R10") (pin "1") (pinfunction "1_1") (pintype "passive"))
    )
    (net (code "189") (name "/NUCLEO_PWM_T3.2") (class "Default")
      (node (ref "R59") (pin "1") (pinfunction "1_1") (pintype "passive"))
    )
    (net (code "190") (name "/NUCLEO_PWM_T3.4") (class "Default")
      (node (ref "R47") (pin "1") (pinfunction "1_1") (pintype "passive"))
    )
    (net (code "191") (name "/NUCLEO_PWM_T4.1") (class "Default")
      (node (ref "R30") (pin "2") (pinfunction "2_2") (pintype "passive"))
    )
    (net (code "192") (name "/NUCLEO_PWM_T4.2") (class "Default")
      (node (ref "R6") (pin "1") (pinfunction "1_1") (pintype "passive"))
    )
    (net (code "193") (name "/NUCLEO_PWM_T4.3") (class "Default")
      (node (ref "R3") (pin "1") (pinfunction "1_1") (pintype "passive"))
    )
    (net (code "194") (name "/NUCLEO_SPI2_MISO") (class "Default")
      (node (ref "R68") (pin "2") (pinfunction "2_2") (pintype "passive"))
    )
    (net (code "195") (name "/NUCLEO_SPI2_MOSI") (class "Default")
      (node (ref "R69") (pin "2") (pinfunction "2_2") (pintype "passive"))
    )
    (net (code "196") (name "/NUCLEO_SPI2_NSS") (class "Default")
      (node (ref "R70") (pin "2") (pinfunction "2_2") (pintype "passive"))
    )
    (net (code "197") (name "/NUCLEO_SPI2_SCK") (class "Default")
      (node (ref "R67") (pin "2") (pinfunction "2_2") (pintype "passive"))
    )
    (net (code "198") (name "/NUCLEO_SPI3_MISO") (class "Default")
      (node (ref "R62") (pin "2") (pinfunction "2_2") (pintype "passive"))
    )
    (net (code "199") (name "/NUCLEO_SPI3_MOSI") (class "Default")
      (node (ref "R63") (pin "2") (pinfunction "2_2") (pintype "passive"))
    )
    (net (code "200") (name "/NUCLEO_SPI3_NSS") (class "Default")
      (node (ref "R82") (pin "2") (pinfunction "2_2") (pintype "passive"))
    )
    (net (code "201") (name "/NUCLEO_SPI3_SCK") (class "Default")
      (node (ref "R61") (pin "2") (pinfunction "2_2") (pintype "passive"))
    )
    (net (code "202") (name "/NUCLEO_UART3_RX") (class "Default")
      (node (ref "R66") (pin "2") (pinfunction "2_2") (pintype "passive"))
    )
    (net (code "203") (name "/NUCLEO_UART3_TX") (class "Default")
      (node (ref "R60") (pin "2") (pinfunction "2_2") (pintype "passive"))
    )
    (net (code "204") (name "/NUCLEO_UART4_RX") (class "Default")
      (node (ref "R14") (pin "1") (pinfunction "1_1") (pintype "passive"))
    )
    (net (code "205") (name "/NUCLEO_UART4_TX") (class "Default")
      (node (ref "R52") (pin "2") (pinfunction "2_2") (pintype "passive"))
    )
    (net (code "206") (name "/NUCLEO_UART5_RX") (class "Default")
      (node (ref "R15") (pin "1") (pinfunction "1_1") (pintype "passive"))
    )
    (net (code "207") (name "/NUCLEO_UART5_TX") (class "Default")
      (node (ref "R53") (pin "2") (pinfunction "2_2") (pintype "passive"))
    )
    (net (code "208") (name "/OLD_HALL_L_L") (class "Default")
      (node (ref "R111") (pin "2") (pinfunction "2_2") (pintype "passive"))
    )
    (net (code "209") (name "/OLD_HALL_L_U") (class "Default")
      (node (ref "R112") (pin "2") (pinfunction "2_2") (pintype "passive"))
    )
    (net (code "210") (name "/OLD_HALL_L_V") (class "Default")
      (node (ref "R95") (pin "1") (pinfunction "1_1") (pintype "passive"))
    )
    (net (code "211") (name "/OLD_HALL_R_L") (class "Default")
      (node (ref "R84") (pin "2") (pinfunction "2_2") (pintype "passive"))
    )
    (net (code "212") (name "/OLD_HALL_R_U") (class "Default")
      (node (ref "R75") (pin "1") (pinfunction "1_1") (pintype "passive"))
    )
    (net (code "213") (name "/OLD_HALL_R_V") (class "Default")
      (node (ref "R73") (pin "1") (pinfunction "1_1") (pintype "passive"))
    )
    (net (code "214") (name "/QEI1_CH_A") (class "Default")
      (node (ref "R71") (pin "2") (pinfunction "2_2") (pintype "passive"))
    )
    (net (code "215") (name "/QEI1_CH_B") (class "Default")
      (node (ref "R72") (pin "2") (pinfunction "2_2") (pintype "passive"))
    )
    (net (code "216") (name "/QEI2_CH_A") (class "Default")
      (node (ref "R54") (pin "2") (pinfunction "2_2") (pintype "passive"))
    )
    (net (code "217") (name "/QEI2_CH_B") (class "Default")
      (node (ref "R55") (pin "2") (pinfunction "2_2") (pintype "passive"))
    )
    (net (code "218") (name "/STM32_PA0") (class "Default")
      (node (ref "CN7") (pin "28") (pinfunction "PA0_28") (pintype "passive"))
      (node (ref "R18") (pin "2") (pinfunction "2_2") (pintype "passive"))
      (node (ref "R57") (pin "2") (pinfunction "2_2") (pintype "passive"))
    )
    (net (code "219") (name "/STM32_PA1") (class "Default")
      (node (ref "CN7") (pin "30") (pinfunction "PA1_30") (pintype "passive"))
      (node (ref "R19") (pin "2") (pinfunction "2_2") (pintype "passive"))
      (node (ref "R58") (pin "2") (pinfunction "2_2") (pintype "passive"))
    )
    (net (code "220") (name "/STM32_PA4") (class "Default")
      (node (ref "CN7") (pin "32") (pinfunction "PA4_32") (pintype "passive"))
      (node (ref "R20") (pin "2") (pinfunction "2_2") (pintype "passive"))
      (node (ref "R59") (pin "2") (pinfunction "2_2") (pintype "passive"))
    )
    (net (code "221") (name "/STM32_PA5") (class "Default")
      (node (ref "CN10") (pin "11") (pinfunction "PF7_11") (pintype "passive"))
      (node (ref "R27") (pin "1") (pinfunction "1_1") (pintype "passive"))
    )
    (net (code "222") (name "/STM32_PA6") (class "Default")
      (node (ref "CN10") (pin "13") (pinfunction "PA13_13") (pintype "passive"))
      (node (ref "R28") (pin "1") (pinfunction "1_1") (pintype "passive"))
    )
    (net (code "223") (name "/STM32_PA7") (class "Default")
      (node (ref "CN10") (pin "15") (pinfunction "PA14_15") (pintype "passive"))
      (node (ref "R29") (pin "1") (pinfunction "1_1") (pintype "passive"))
    )
    (net (code "224") (name "/STM32_PA8") (class "Default")
      (node (ref "CN10") (pin "23") (pinfunction "PC13_23") (pintype "passive"))
      (node (ref "R33") (pin "1") (pinfunction "1_1") (pintype "passive"))
      (node (ref "R72") (pin "1") (pinfunction "1_1") (pintype "passive"))
    )
    (net (code "225") (name "/STM32_PA9") (class "Default")
      (node (ref "CN10") (pin "21") (pinfunction "PB7_21") (pintype "passive"))
      (node (ref "R32") (pin "1") (pinfunction "1_1") (pintype "passive"))
      (node (ref "R71") (pin "1") (pinfunction "1_1") (pintype "passive"))
    )
    (net (code "226") (name "/STM32_PA10") (class "Default")
      (node (ref "CN10") (pin "33") (pinfunction "VBAT_33") (pintype "passive"))
      (node (ref "R38") (pin "1") (pinfunction "1_1") (pintype "passive"))
    )
    (net (code "227") (name "/STM32_PA11") (class "Default")
      (node (ref "CN10") (pin "14") (pinfunction "NRST_14") (pintype "passive"))
      (node (ref "R43") (pin "2") (pinfunction "2_2") (pintype "passive"))
    )
    (net (code "228") (name "/STM32_PA12") (class "Default")
      (node (ref "CN10") (pin "12") (pinfunction "+3V3_12") (pintype "passive"))
      (node (ref "R42") (pin "2") (pinfunction "2_2") (pintype "passive"))
    )
    (net (code "229") (name "/STM32_PA13") (class "Default")
      (node (ref "CN7") (pin "13") (pinfunction "PA13_13") (pintype "passive"))
      (node (ref "R3") (pin "2") (pinfunction "2_2") (pintype "passive"))
    )
    (net (code "230") (name "/STM32_PA14") (class "Default")
      (node (ref "CN7") (pin "15") (pinfunction "PA14_15") (pintype "passive"))
      (node (ref "R4") (pin "2") (pinfunction "2_2") (pintype "passive"))
      (node (ref "R55") (pin "1") (pinfunction "1_1") (pintype "passive"))
    )
    (net (code "231") (name "/STM32_PA15") (class "Default")
      (node (ref "CN7") (pin "17") (pinfunction "PA15_17") (pintype "passive"))
      (node (ref "R5") (pin "2") (pinfunction "2_2") (pintype "passive"))
      (node (ref "R54") (pin "1") (pinfunction "1_1") (pintype "passive"))
    )
    (net (code "232") (name "/STM32_PB0") (class "Default")
      (node (ref "CN7") (pin "34") (pinfunction "PB0_34") (pintype "passive"))
      (node (ref "R21") (pin "2") (pinfunction "2_2") (pintype "passive"))
    )
    (net (code "233") (name "/STM32_PB1") (class "Default")
      (node (ref "CN10") (pin "24") (pinfunction "VIN_24") (pintype "passive"))
      (node (ref "R47") (pin "2") (pinfunction "2_2") (pintype "passive"))
    )
    (net (code "234") (name "/STM32_PB2") (class "Default")
      (node (ref "CN10") (pin "22") (pinfunction "GND_22") (pintype "passive"))
      (node (ref "R46") (pin "2") (pinfunction "2_2") (pintype "passive"))
      (node (ref "R65") (pin "1") (pinfunction "1_1") (pintype "passive"))
    )
    (net (code "235") (name "/STM32_PB3") (class "Default")
      (node (ref "CN10") (pin "31") (pinfunction "PD1/PH1/PF1_31") (pintype "passive"))
      (node (ref "R37") (pin "1") (pinfunction "1_1") (pintype "passive"))
      (node (ref "R61") (pin "1") (pinfunction "1_1") (pintype "passive"))
    )
    (net (code "236") (name "/STM32_PB4") (class "Default")
      (node (ref "CN10") (pin "27") (pinfunction "PC15_27") (pintype "passive"))
      (node (ref "R35") (pin "1") (pinfunction "1_1") (pintype "passive"))
      (node (ref "R62") (pin "1") (pinfunction "1_1") (pintype "passive"))
    )
    (net (code "237") (name "/STM32_PB5") (class "Default")
      (node (ref "CN10") (pin "29") (pinfunction "PD0/PH0/PF0_29") (pintype "passive"))
      (node (ref "R36") (pin "1") (pinfunction "1_1") (pintype "passive"))
      (node (ref "R63") (pin "1") (pinfunction "1_1") (pintype "passive"))
    )
    (net (code "238") (name "/STM32_PB6") (class "Default")
      (node (ref "CN10") (pin "17") (pinfunction "PA15_17") (pintype "passive"))
      (node (ref "R30") (pin "1") (pinfunction "1_1") (pintype "passive"))
    )
    (net (code "239") (name "/STM32_PB7") (class "Default")
      (node (ref "CN7") (pin "21") (pinfunction "PB7_21") (pintype "passive"))
      (node (ref "R6") (pin "2") (pinfunction "2_2") (pintype "passive"))
    )
    (net (code "240") (name "/STM32_PB8") (class "Default")
      (node (ref "CN10") (pin "3") (pinfunction "PC12_3") (pintype "passive"))
      (node (ref "R25") (pin "1") (pinfunction "1_1") (pintype "passive"))
    )
    (net (code "241") (name "/STM32_PB9") (class "Default")
      (node (ref "CN10") (pin "5") (pinfunction "VDD_5") (pintype "passive"))
      (node (ref "R26") (pin "1") (pinfunction "1_1") (pintype "passive"))
    )
    (net (code "242") (name "/STM32_PB10") (class "Default")
      (node (ref "CN10") (pin "25") (pinfunction "PC14_25") (pintype "passive"))
      (node (ref "R34") (pin "1") (pinfunction "1_1") (pintype "passive"))
      (node (ref "R60") (pin "1") (pinfunction "1_1") (pintype "passive"))
    )
    (net (code "243") (name "/STM32_PB11") (class "Default")
      (node (ref "CN10") (pin "18") (pinfunction "+5V_18") (pintype "passive"))
      (node (ref "R45") (pin "2") (pinfunction "2_2") (pintype "passive"))
      (node (ref "R66") (pin "1") (pinfunction "1_1") (pintype "passive"))
    )
    (net (code "244") (name "/STM32_PB12") (class "Default")
      (node (ref "CN10") (pin "16") (pinfunction "+3V3_16") (pintype "passive"))
      (node (ref "R44") (pin "2") (pinfunction "2_2") (pintype "passive"))
      (node (ref "R70") (pin "1") (pinfunction "1_1") (pintype "passive"))
    )
    (net (code "245") (name "/STM32_PB13") (class "Default")
      (node (ref "CN10") (pin "30") (pinfunction "PA1_30") (pintype "passive"))
      (node (ref "R50") (pin "2") (pinfunction "2_2") (pintype "passive"))
      (node (ref "R67") (pin "1") (pinfunction "1_1") (pintype "passive"))
    )
    (net (code "246") (name "/STM32_PB14") (class "Default")
      (node (ref "CN10") (pin "28") (pinfunction "PA0_28") (pintype "passive"))
      (node (ref "R49") (pin "2") (pinfunction "2_2") (pintype "passive"))
      (node (ref "R68") (pin "1") (pinfunction "1_1") (pintype "passive"))
    )
    (net (code "247") (name "/STM32_PB15") (class "Default")
      (node (ref "CN10") (pin "26") (pintype "passive"))
      (node (ref "R48") (pin "2") (pinfunction "2_2") (pintype "passive"))
      (node (ref "R69") (pin "1") (pinfunction "1_1") (pintype "passive"))
    )
    (net (code "248") (name "/STM32_PC0") (class "Default")
      (node (ref "CN7") (pin "38") (pinfunction "PC0/PB9_38") (pintype "passive"))
      (node (ref "R23") (pin "2") (pinfunction "2_2") (pintype "passive"))
    )
    (net (code "249") (name "/STM32_PC1") (class "Default")
      (node (ref "CN7") (pin "36") (pinfunction "PC1/PB8_36") (pintype "passive"))
      (node (ref "R22") (pin "2") (pinfunction "2_2") (pintype "passive"))
    )
    (net (code "250") (name "/STM32_PC2") (class "Default")
      (node (ref "CN7") (pin "35") (pinfunction "PC2_35") (pintype "passive"))
      (node (ref "R12") (pin "1") (pinfunction "1_1") (pintype "passive"))
    )
    (net (code "251") (name "/STM32_PC3") (class "Default")
      (node (ref "CN7") (pin "37") (pinfunction "PC3_37") (pintype "passive"))
      (node (ref "R13") (pin "1") (pinfunction "1_1") (pintype "passive"))
    )
    (net (code "252") (name "/STM32_PC4") (class "Default")
      (node (ref "CN10") (pin "34") (pinfunction "PB0_34") (pintype "passive"))
      (node (ref "R51") (pin "2") (pinfunction "2_2") (pintype "passive"))
    )
    (net (code "253") (name "/STM32_PC5") (class "Default")
      (node (ref "CN10") (pin "6") (pinfunction "E5V_6") (pintype "passive"))
      (node (ref "R41") (pin "2") (pinfunction "2_2") (pintype "passive"))
    )
    (net (code "254") (name "/STM32_PC6") (class "Default")
      (node (ref "CN10") (pin "4") (pinfunction "PD2_4") (pintype "passive"))
      (node (ref "R40") (pin "2") (pinfunction "2_2") (pintype "passive"))
    )
    (net (code "255") (name "/STM32_PC7") (class "Default")
      (node (ref "CN10") (pin "19") (pinfunction "GND_19") (pintype "passive"))
      (node (ref "R31") (pin "1") (pinfunction "1_1") (pintype "passive"))
      (node (ref "R64") (pin "2") (pinfunction "2_2") (pintype "passive"))
    )
    (net (code "256") (name "/STM32_PC8") (class "Default")
      (node (ref "CN10") (pin "2") (pinfunction "PC11_2") (pintype "passive"))
      (node (ref "R39") (pin "2") (pinfunction "2_2") (pintype "passive"))
    )
    (net (code "257") (name "/STM32_PC9") (class "Default")
      (node (ref "CN10") (pin "1") (pinfunction "PC10_1") (pintype "passive"))
      (node (ref "R24") (pin "1") (pinfunction "1_1") (pintype "passive"))
    )
    (net (code "258") (name "/STM32_PC10") (class "Default")
      (node (ref "CN7") (pin "1") (pinfunction "PC10_1") (pintype "passive"))
      (node (ref "R1") (pin "2") (pinfunction "2_2") (pintype "passive"))
      (node (ref "R52") (pin "1") (pinfunction "1_1") (pintype "passive"))
    )
    (net (code "259") (name "/STM32_PC11") (class "Default")
      (node (ref "CN7") (pin "2") (pinfunction "PC11_2") (pintype "passive"))
      (node (ref "R14") (pin "2") (pinfunction "2_2") (pintype "passive"))
      (node (ref "R16") (pin "2") (pinfunction "2_2") (pintype "passive"))
    )
    (net (code "260") (name "/STM32_PC12") (class "Default")
      (node (ref "CN7") (pin "3") (pinfunction "PC12_3") (pintype "passive"))
      (node (ref "R2") (pin "2") (pinfunction "2_2") (pintype "passive"))
      (node (ref "R53") (pin "1") (pinfunction "1_1") (pintype "passive"))
    )
    (net (code "261") (name "/STM32_PC13") (class "Default")
      (node (ref "CN7") (pin "23") (pinfunction "PC13_23") (pintype "passive"))
      (node (ref "R7") (pin "2") (pinfunction "2_2") (pintype "passive"))
    )
    (net (code "262") (name "/STM32_PC14") (class "Default")
      (node (ref "CN7") (pin "25") (pinfunction "PC14_25") (pintype "passive"))
      (node (ref "R8") (pin "2") (pinfunction "2_2") (pintype "passive"))
    )
    (net (code "263") (name "/STM32_PC15") (class "Default")
      (node (ref "CN7") (pin "27") (pinfunction "PC15_27") (pintype "passive"))
      (node (ref "R56") (pin "1") (pinfunction "1_1") (pintype "passive"))
      (node (ref "R9") (pin "2") (pinfunction "2_2") (pintype "passive"))
    )
    (net (code "264") (name "/STM32_PD2") (class "Default")
      (node (ref "CN7") (pin "4") (pinfunction "PD2_4") (pintype "passive"))
      (node (ref "R15") (pin "2") (pinfunction "2_2") (pintype "passive"))
      (node (ref "R17") (pin "2") (pinfunction "2_2") (pintype "passive"))
    )
    (net (code "265") (name "/STM32_PF0") (class "Default")
      (node (ref "CN7") (pin "29") (pinfunction "PD0/PH0/PF0_29") (pintype "passive"))
      (node (ref "R10") (pin "2") (pinfunction "2_2") (pintype "passive"))
    )
    (net (code "266") (name "/STM32_PF1") (class "Default")
      (node (ref "CN7") (pin "31") (pinfunction "PD1/PH1/PF1_31") (pintype "passive"))
      (node (ref "R11") (pin "1") (pinfunction "1_1") (pintype "passive"))
    )
    (net (code "267") (name "5V") (class "Default")
      (node (ref "C3") (pin "2") (pinfunction "2_2") (pintype "passive"))
      (node (ref "XM1") (pin "1") (pinfunction "VCC_5V_1") (pintype "power_in"))
    )
    (net (code "268") (name "5V_USB_NUCLEO") (class "Default")
      (node (ref "CN10") (pin "8") (pinfunction "GND_8") (pintype "passive"))
    )
    (net (code "269") (name "GND") (class "Default")
      (node (ref "C3") (pin "1") (pinfunction "1_1") (pintype "passive"))
      (node (ref "CN10") (pin "20") (pinfunction "GND_20") (pintype "passive"))
      (node (ref "CN10") (pin "32") (pinfunction "PA4_32") (pintype "passive"))
      (node (ref "CN10") (pin "9") (pinfunction "PF6_9") (pintype "passive"))
      (node (ref "CN7") (pin "19") (pinfunction "GND_19") (pintype "passive"))
      (node (ref "CN7") (pin "20") (pinfunction "GND_20") (pintype "passive"))
      (node (ref "CN7") (pin "22") (pinfunction "GND_22") (pintype "passive"))
      (node (ref "CN7") (pin "8") (pinfunction "GND_8") (pintype "passive"))
      (node (ref "XM1") (pin "112") (pinfunction "GND_112") (pintype "power_in"))
      (node (ref "XM1") (pin "130") (pinfunction "GND_130") (pintype "power_in"))
      (node (ref "XM1") (pin "2") (pinfunction "GND_2") (pintype "power_in"))
      (node (ref "XM1") (pin "212") (pinfunction "GND_212") (pintype "power_in"))
      (node (ref "XM1") (pin "230") (pinfunction "GND_230") (pintype "power_in"))
      (node (ref "XM1") (pin "326") (pinfunction "GND_326") (pintype "power_in"))
    )
    (net (code "270") (name "unconnected-(CN7-+3V3-Pad12)") (class "Default")
      (node (ref "CN7") (pin "12") (pinfunction "+3V3_12") (pintype "passive"))
    )
    (net (code "271") (name "unconnected-(CN7-+3V3-Pad16)") (class "Default")
      (node (ref "CN7") (pin "16") (pinfunction "+3V3_16") (pintype "passive"))
    )
    (net (code "272") (name "unconnected-(CN7-+5V-Pad18)") (class "Default")
      (node (ref "CN7") (pin "18") (pinfunction "+5V_18") (pintype "passive"))
    )
    (net (code "273") (name "unconnected-(CN7-BOOT0-Pad7)") (class "Default")
      (node (ref "CN7") (pin "7") (pinfunction "BOOT0_7") (pintype "passive"))
    )
    (net (code "274") (name "unconnected-(CN7-E5V-Pad6)") (class "Default")
      (node (ref "CN7") (pin "6") (pinfunction "E5V_6") (pintype "passive"))
    )
    (net (code "275") (name "unconnected-(CN7-NRST-Pad14)") (class "Default")
      (node (ref "CN7") (pin "14") (pinfunction "NRST_14") (pintype "passive"))
    )
    (net (code "276") (name "unconnected-(CN7-PF6-Pad9)") (class "Default")
      (node (ref "CN7") (pin "9") (pinfunction "PF6_9") (pintype "passive"))
    )
    (net (code "277") (name "unconnected-(CN7-PF7-Pad11)") (class "Default")
      (node (ref "CN7") (pin "11") (pinfunction "PF7_11") (pintype "passive"))
    )
    (net (code "278") (name "unconnected-(CN7-Pad10)") (class "Default")
      (node (ref "CN7") (pin "10") (pintype "passive"))
    )
    (net (code "279") (name "unconnected-(CN7-Pad26)") (class "Default")
      (node (ref "CN7") (pin "26") (pintype "passive"))
    )
    (net (code "280") (name "unconnected-(CN7-VBAT-Pad33)") (class "Default")
      (node (ref "CN7") (pin "33") (pinfunction "VBAT_33") (pintype "passive"))
    )
    (net (code "281") (name "unconnected-(CN7-VDD-Pad5)") (class "Default")
      (node (ref "CN7") (pin "5") (pinfunction "VDD_5") (pintype "passive"))
    )
    (net (code "282") (name "unconnected-(CN7-VIN-Pad24)") (class "Default")
      (node (ref "CN7") (pin "24") (pinfunction "VIN_24") (pintype "passive"))
    )
    (net (code "283") (name "unconnected-(CN10-BOOT0-Pad7)") (class "Default")
      (node (ref "CN10") (pin "7") (pinfunction "BOOT0_7") (pintype "passive"))
    )
    (net (code "284") (name "unconnected-(CN10-PC0{slash}PB9-Pad38)") (class "Default")
      (node (ref "CN10") (pin "38") (pinfunction "PC0/PB9_38") (pintype "passive"))
    )
    (net (code "285") (name "unconnected-(CN10-PC1{slash}PB8-Pad36)") (class "Default")
      (node (ref "CN10") (pin "36") (pinfunction "PC1/PB8_36") (pintype "passive"))
    )
    (net (code "286") (name "unconnected-(CN10-PC2-Pad35)") (class "Default")
      (node (ref "CN10") (pin "35") (pinfunction "PC2_35") (pintype "passive"))
    )
    (net (code "287") (name "unconnected-(CN10-PC3-Pad37)") (class "Default")
      (node (ref "CN10") (pin "37") (pinfunction "PC3_37") (pintype "passive"))
    )
    (net (code "288") (name "unconnected-(CN10-Pad10)") (class "Default")
      (node (ref "CN10") (pin "10") (pintype "passive"))
    )
    (net (code "289") (name "unconnected-(XM1-VCC_3V3-Pad129)") (class "Default")
      (node (ref "XM1") (pin "129") (pinfunction "VCC_3V3_129") (pintype "power_in"))
    )
    (net (code "290") (name "unconnected-(XM1-VCC_3V3-Pad229)") (class "Default")
      (node (ref "XM1") (pin "229") (pinfunction "VCC_3V3_229") (pintype "power_in"))
    )
    (net (code "291") (name "unconnected-(XM1-VCC_3V3-Pad301)") (class "Default")
      (node (ref "XM1") (pin "301") (pinfunction "VCC_3V3_301") (pintype "power_in"))
    )
    (net (code "292") (name "unconnected-(XM1-VCC_5V-Pad111)") (class "Default")
      (node (ref "XM1") (pin "111") (pinfunction "VCC_5V_111") (pintype "power_in"))
    )
    (net (code "293") (name "unconnected-(XM1-VCC_5V-Pad211)") (class "Default")
      (node (ref "XM1") (pin "211") (pinfunction "VCC_5V_211") (pintype "power_in"))
    )
    (net (code "294") (name "unconnected-(XM1-nc-Pad12)") (class "Default")
      (node (ref "XM1") (pin "12") (pinfunction "nc_12") (pintype "passive"))
    )
  )
)
